# CS-HAT_V2.net
KiCad netlist of a schematic drawn in EAGLE
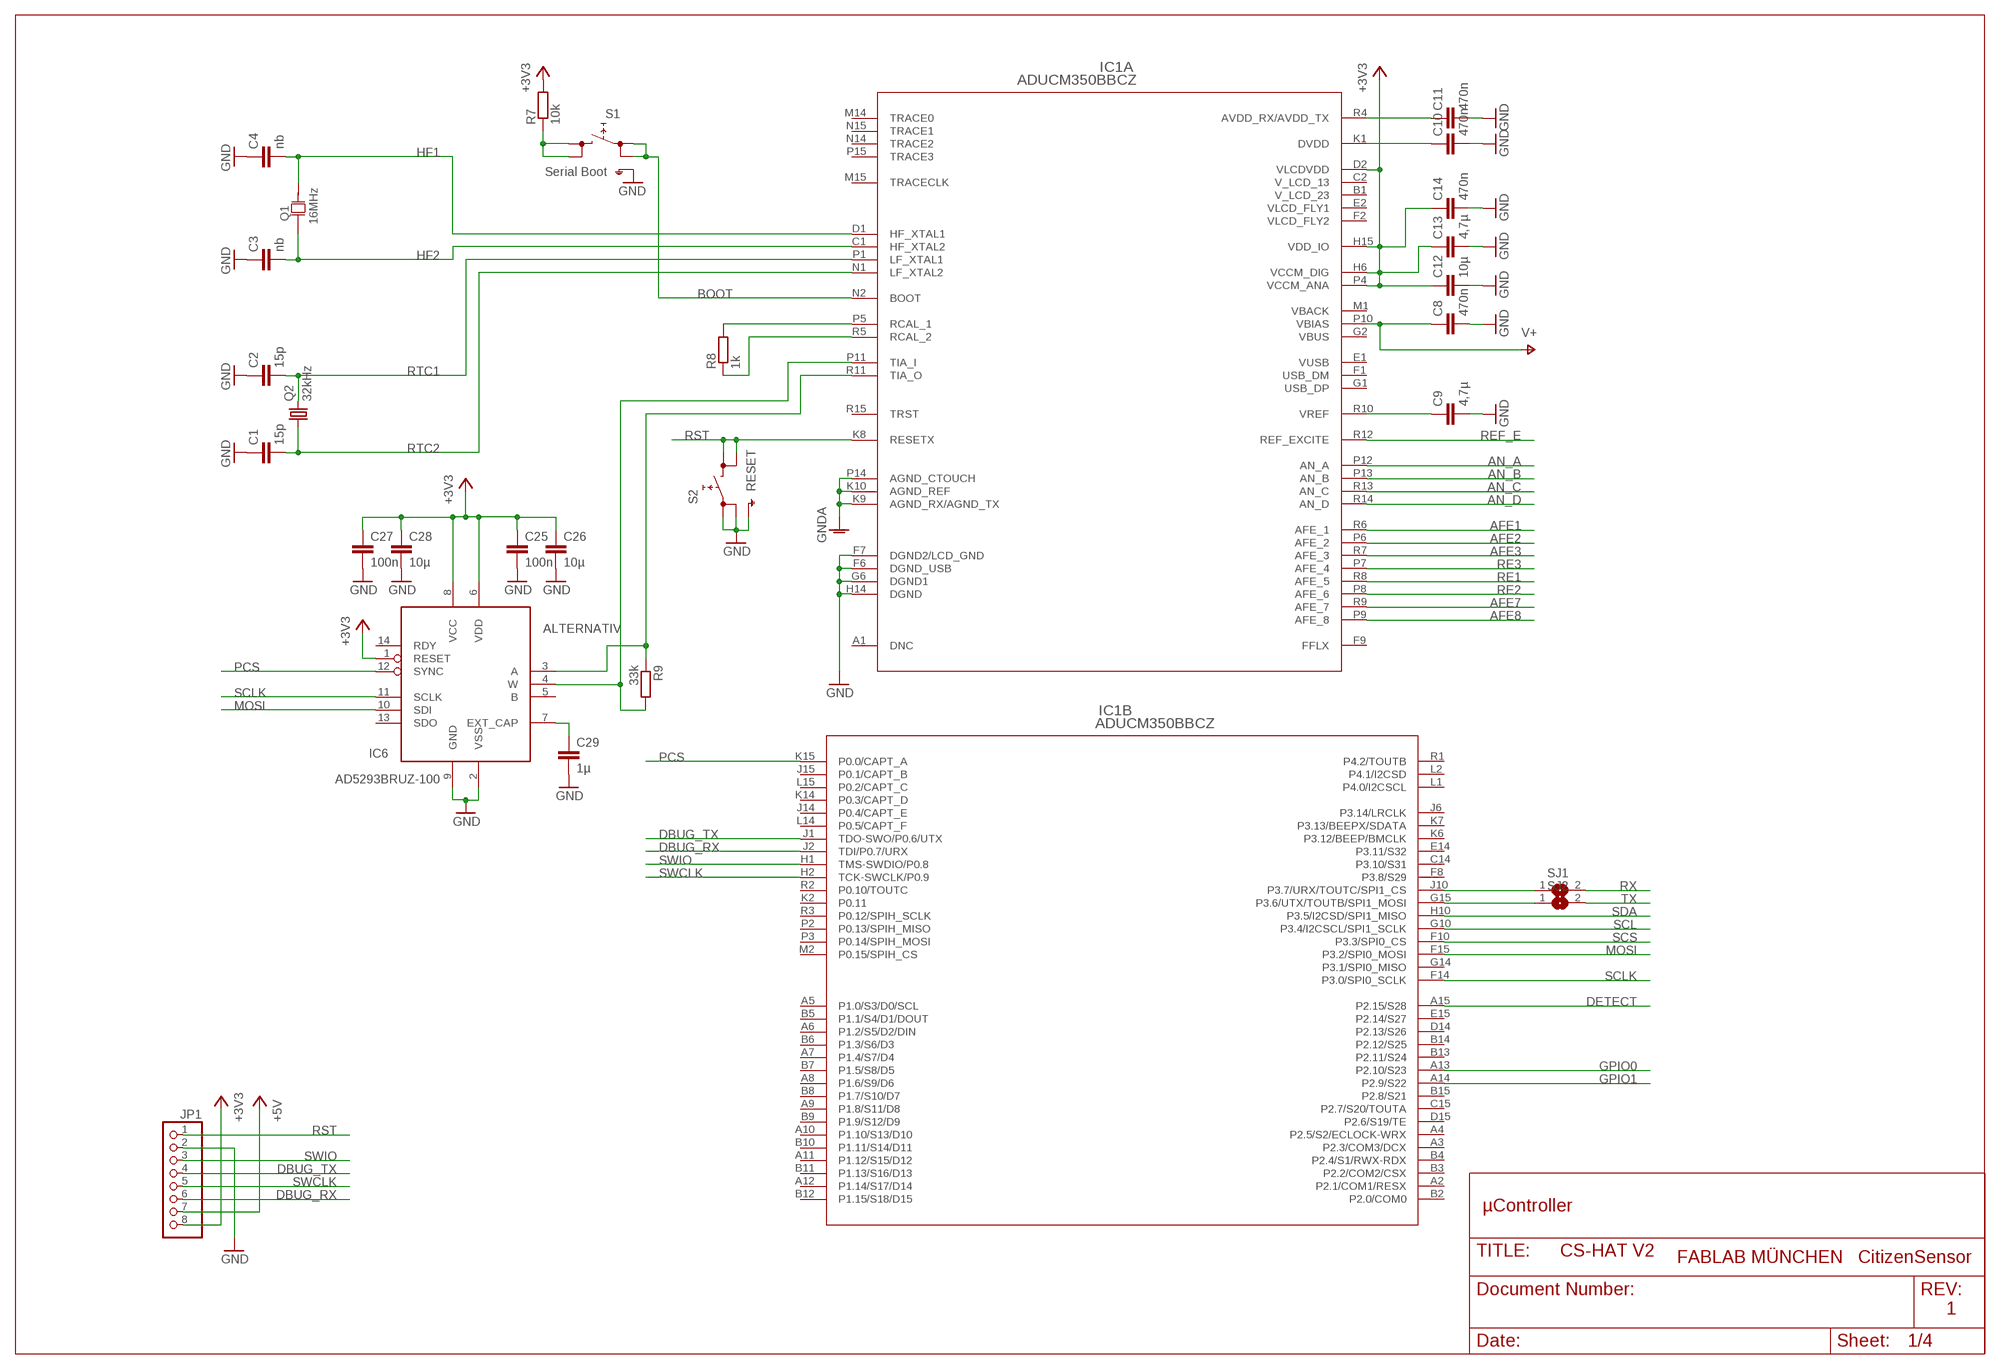
[diagram p0: schematic, sheet 1]
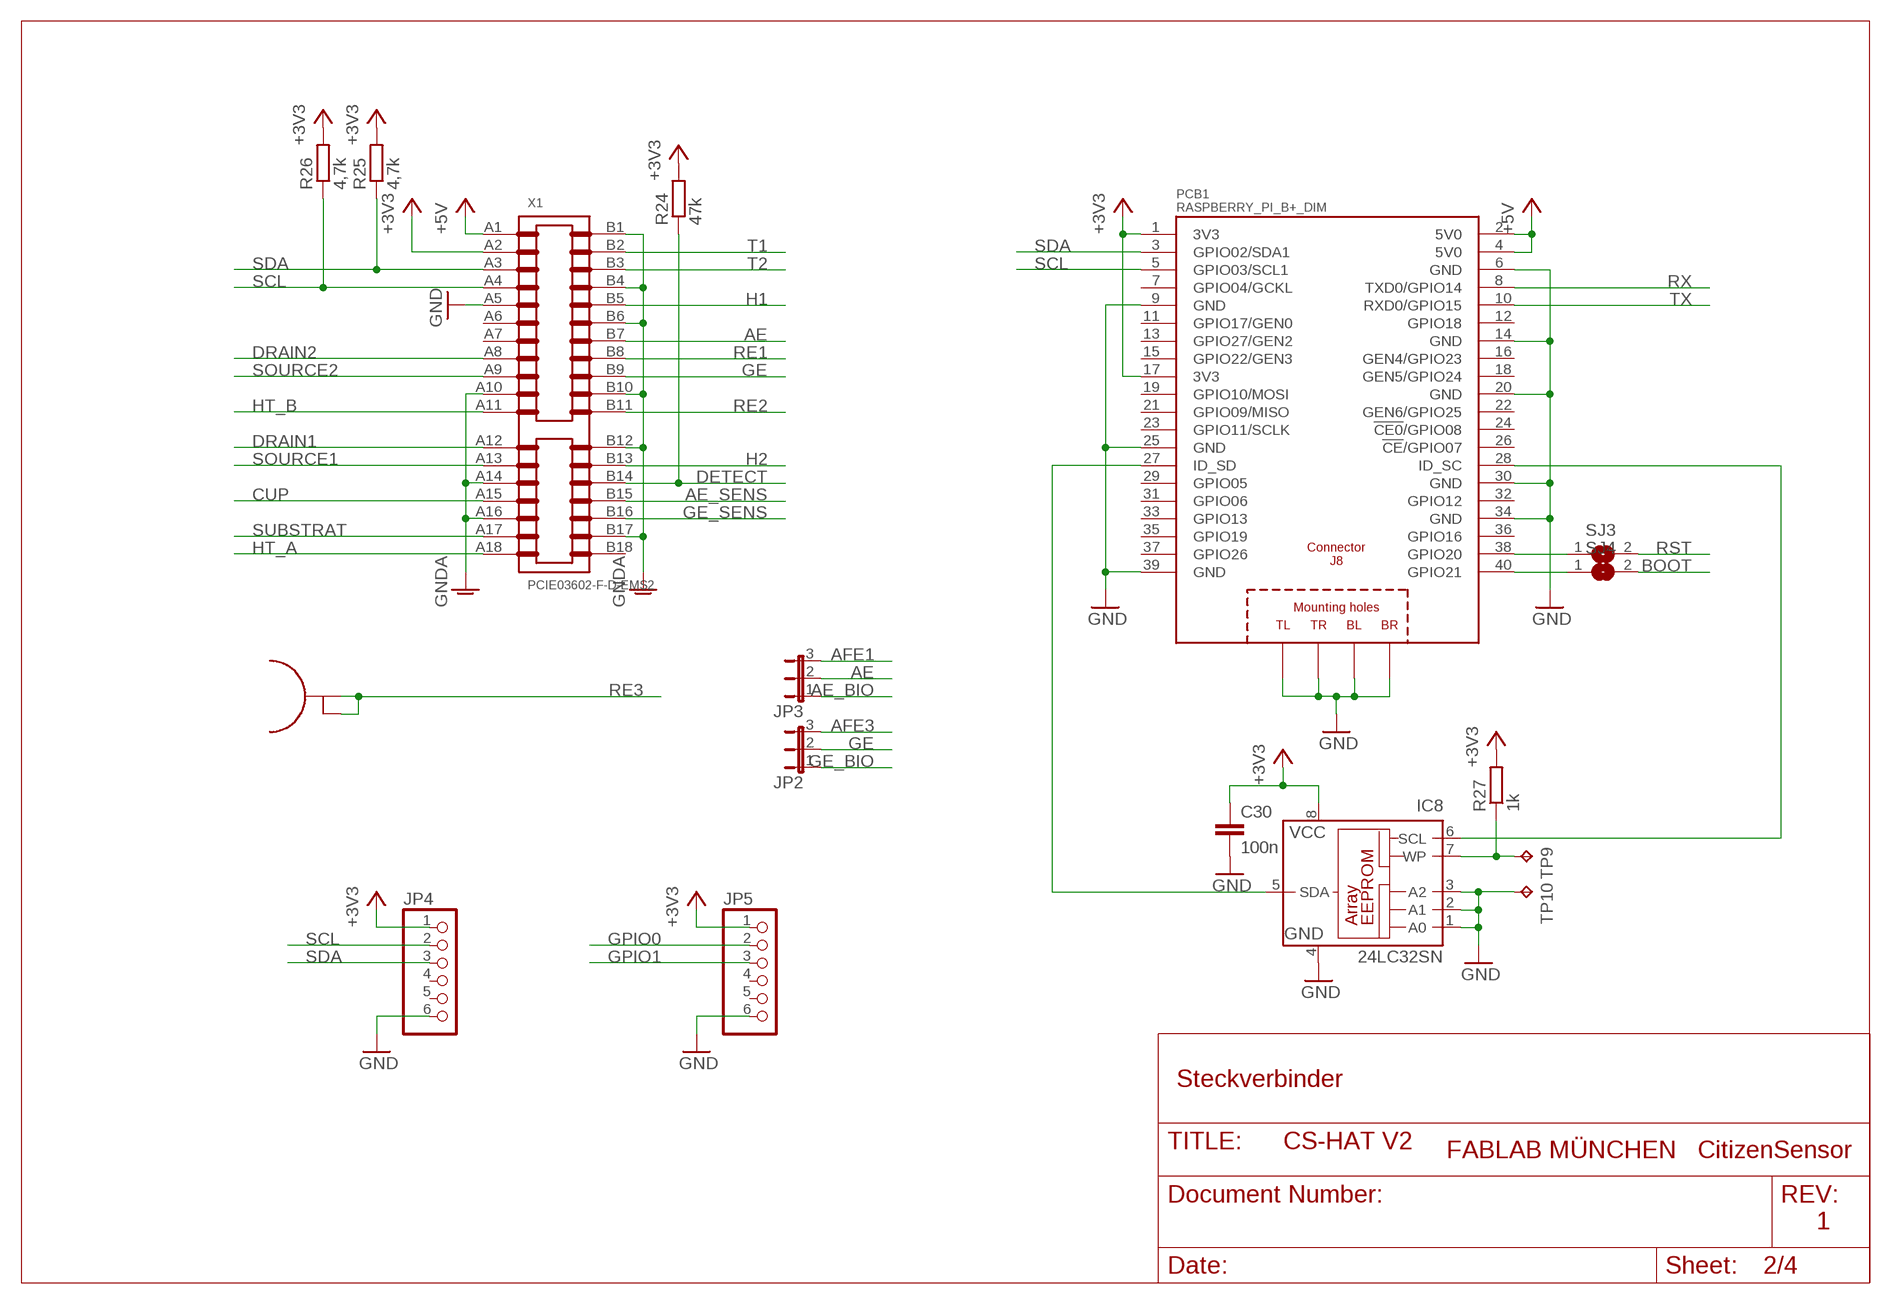
[diagram p1: schematic, sheet 2]
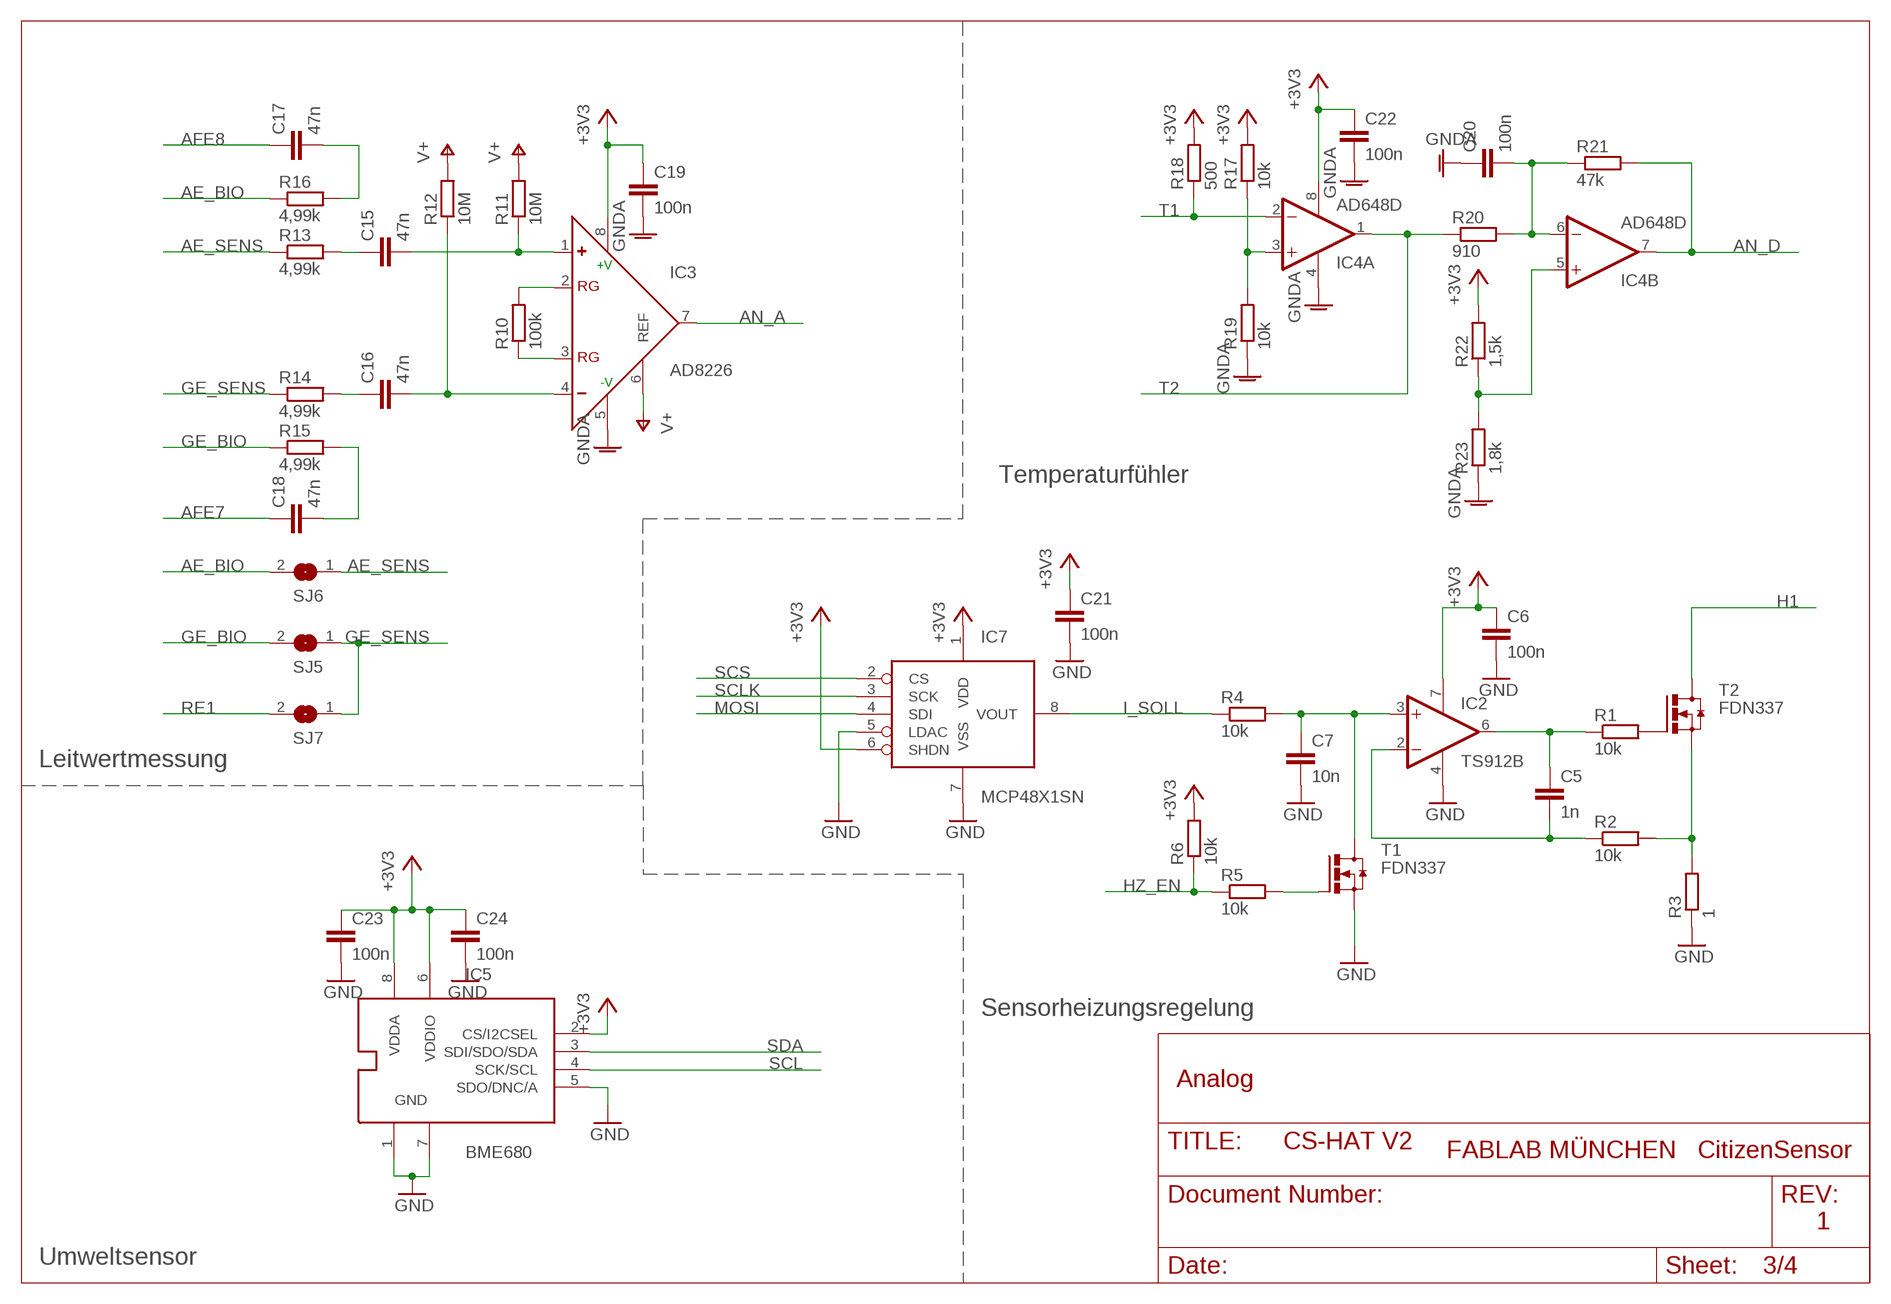
[diagram p2: schematic, sheet 3]
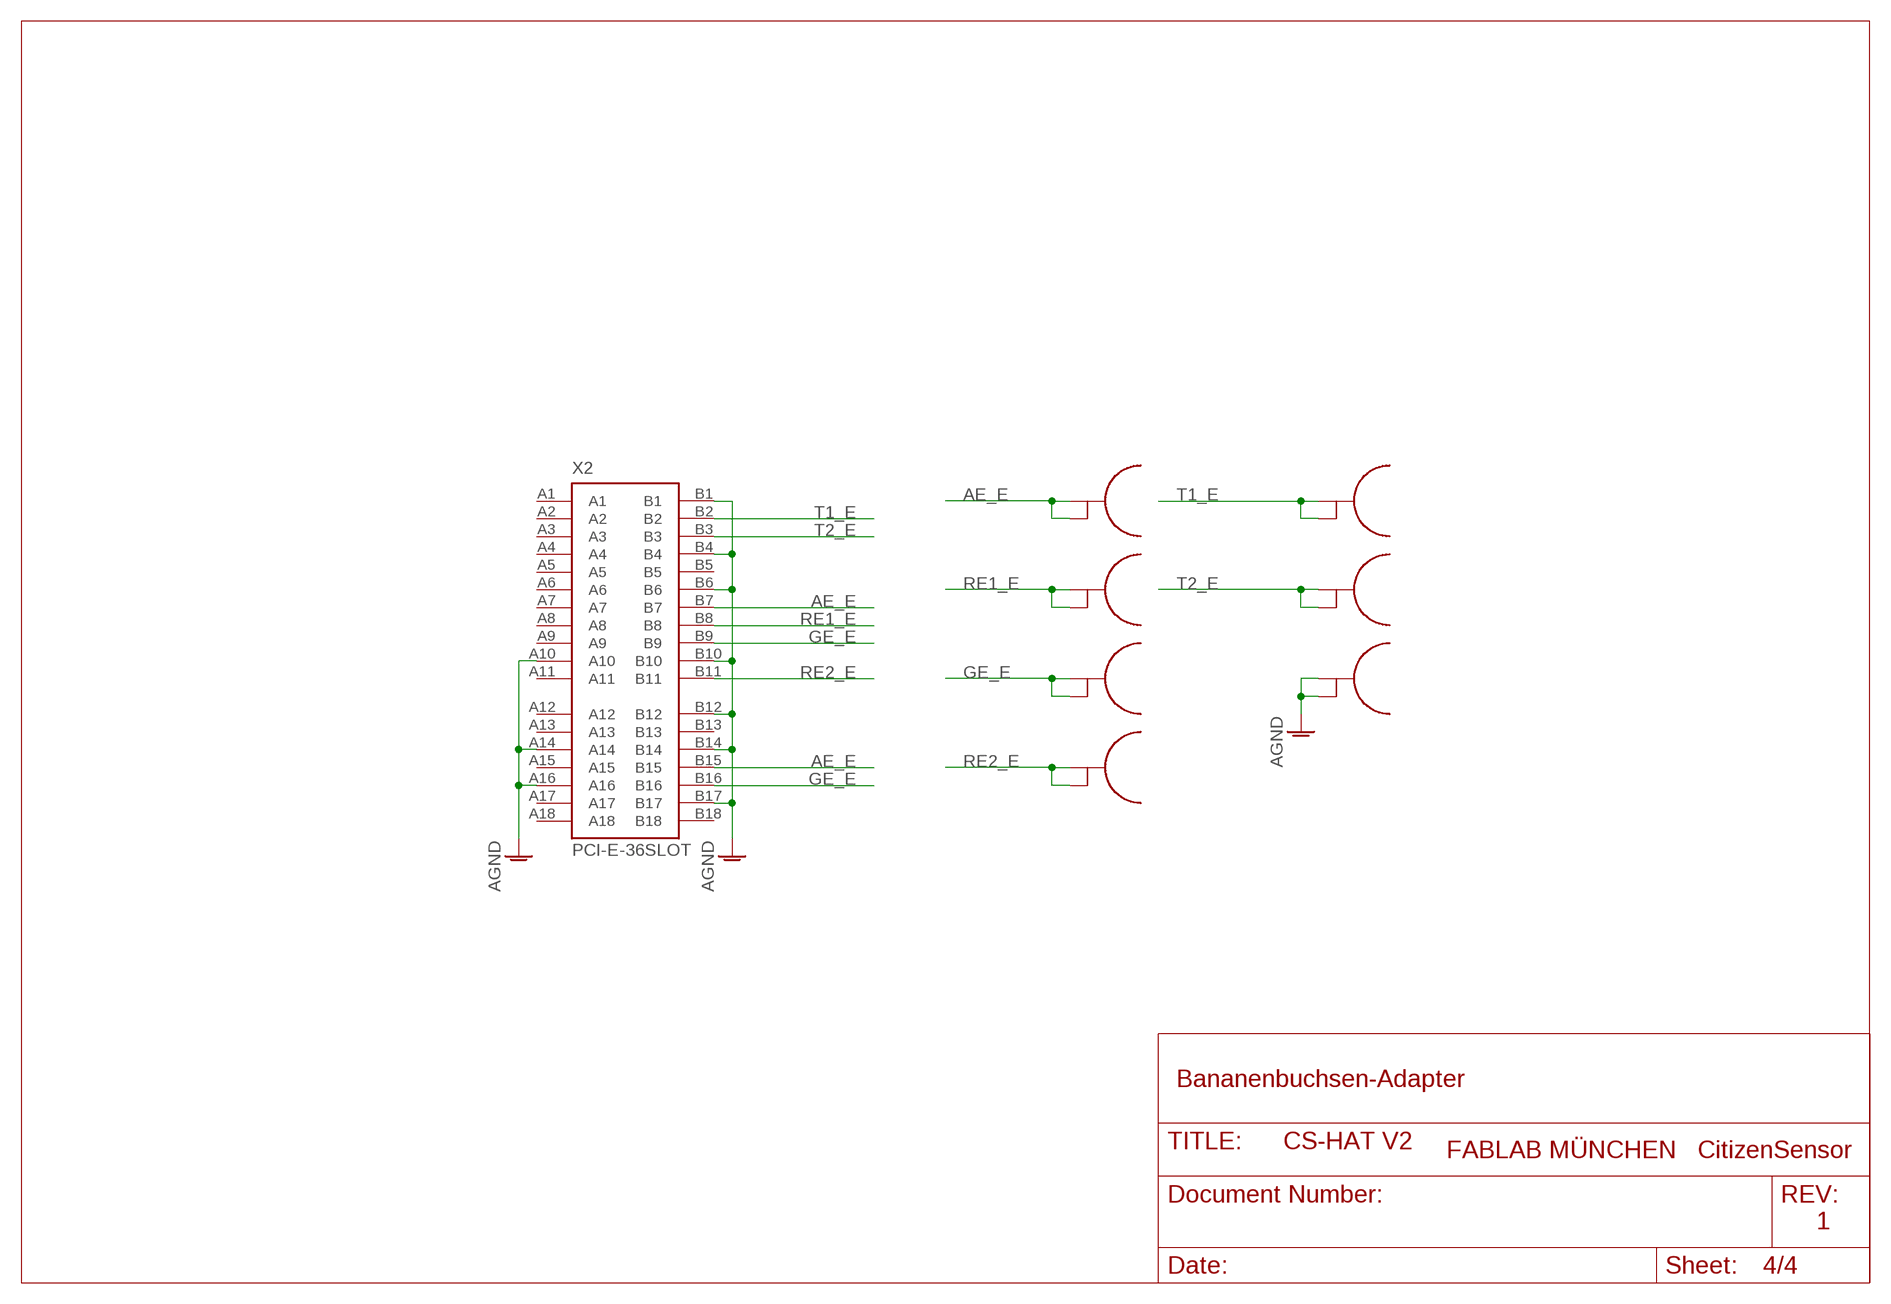
[diagram p3: schematic, sheet 4]

(export (version "E")
  (design (tool "Eeschema 10.0.6"))
  (components
    (comp (ref "C30")
      (value "100n")
      (footprint "eagle-import:C0805")
      (libsource (lib "eagle-import") (part "C-EUC0805"))
    )
    (comp (ref "IC8")
      (value "24LC32SN")
      (footprint "eagle-import:SO-08")
      (fields (field (name "MPN") "M24C04-WMN6P"))
      (libsource (lib "eagle-import") (part "24CSN04"))
    )
    (comp (ref "JP2")
      (value "JP2ES")
      (footprint "eagle-import:JP2S")
      (libsource (lib "eagle-import") (part "JP2ES"))
    )
    (comp (ref "JP3")
      (value "JP2ES")
      (footprint "eagle-import:JP2S")
      (libsource (lib "eagle-import") (part "JP2ES"))
    )
    (comp (ref "JP4")
      (value "PINHD-1X6S")
      (footprint "eagle-import:1X06S")
      (libsource (lib "eagle-import") (part "PINHD-1X6S"))
    )
    (comp (ref "JP5")
      (value "PINHD-1X6S")
      (footprint "eagle-import:1X06S")
      (libsource (lib "eagle-import") (part "PINHD-1X6S"))
    )
    (comp (ref "PCB1")
      (value "RASPBERRY_PI_B+_DIM")
      (footprint "eagle-import:RASPBERRY_PI_BPLUS_DIM")
      (libsource (lib "eagle-import") (part "RASPBERRY_PI_B+_DIM"))
    )
    (comp (ref "R24")
      (value "47k")
      (footprint "eagle-import:R0805")
      (libsource (lib "eagle-import") (part "R-EU_R0805"))
    )
    (comp (ref "R25")
      (value "4,7k")
      (footprint "eagle-import:R0805")
      (libsource (lib "eagle-import") (part "R-EU_R0805"))
    )
    (comp (ref "R26")
      (value "4,7k")
      (footprint "eagle-import:R0805")
      (libsource (lib "eagle-import") (part "R-EU_R0805"))
    )
    (comp (ref "R27")
      (value "1k")
      (footprint "eagle-import:R0805")
      (libsource (lib "eagle-import") (part "R-EU_R0805"))
    )
    (comp (ref "SJ3") (value "SJ") (footprint "eagle-import:SJ") (libsource (lib "eagle-import") (part "SJ")))
    (comp (ref "SJ4") (value "SJ") (footprint "eagle-import:SJ") (libsource (lib "eagle-import") (part "SJ")))
    (comp (ref "TP8")
      (value "TESTPLUG2MM")
      (footprint "eagle-import:TESTPLUG2MM")
      (libsource (lib "eagle-import") (part "TESTPLUG2MM"))
    )
    (comp (ref "TP9")
      (value "TPB2,54")
      (footprint "eagle-import:B2,54")
      (libsource (lib "eagle-import") (part "TPB2,54"))
    )
    (comp (ref "TP10")
      (value "TPB2,54")
      (footprint "eagle-import:B2,54")
      (libsource (lib "eagle-import") (part "TPB2,54"))
    )
    (comp (ref "X1")
      (value "PCIE03602-F-D-EMS2")
      (footprint "eagle-import:PCIE-036-02-F-D-EMS2")
      (libsource (lib "eagle-import") (part "PCIE03602-F-D-EMS2"))
    )
    (comp (ref "C1")
      (value "15p")
      (footprint "eagle-import:C0805")
      (libsource (lib "eagle-import") (part "C-EUC0805"))
    )
    (comp (ref "C2")
      (value "15p")
      (footprint "eagle-import:C0805")
      (libsource (lib "eagle-import") (part "C-EUC0805"))
    )
    (comp (ref "C3")
      (value "nb")
      (footprint "eagle-import:C0805")
      (libsource (lib "eagle-import") (part "C-EUC0805"))
    )
    (comp (ref "C4")
      (value "nb")
      (footprint "eagle-import:C0805")
      (libsource (lib "eagle-import") (part "C-EUC0805"))
    )
    (comp (ref "C8")
      (value "470n")
      (footprint "eagle-import:C0805")
      (libsource (lib "eagle-import") (part "C-EUC0805"))
    )
    (comp (ref "C9")
      (value "4,7µ")
      (footprint "eagle-import:C1206")
      (libsource (lib "eagle-import") (part "C-EUC1206"))
    )
    (comp (ref "C10")
      (value "470n")
      (footprint "eagle-import:C0805")
      (libsource (lib "eagle-import") (part "C-EUC0805"))
    )
    (comp (ref "C11")
      (value "470n")
      (footprint "eagle-import:C0805")
      (libsource (lib "eagle-import") (part "C-EUC0805"))
    )
    (comp (ref "C12")
      (value "10µ")
      (footprint "eagle-import:C1206")
      (libsource (lib "eagle-import") (part "C-EUC1206"))
    )
    (comp (ref "C13")
      (value "4,7µ")
      (footprint "eagle-import:C1206")
      (libsource (lib "eagle-import") (part "C-EUC1206"))
    )
    (comp (ref "C14")
      (value "470n")
      (footprint "eagle-import:C0805")
      (libsource (lib "eagle-import") (part "C-EUC0805"))
    )
    (comp (ref "C25")
      (value "100n")
      (footprint "eagle-import:C0805")
      (libsource (lib "eagle-import") (part "C-EUC0805"))
    )
    (comp (ref "C26")
      (value "10µ")
      (footprint "eagle-import:C1206")
      (libsource (lib "eagle-import") (part "C-EUC1206"))
    )
    (comp (ref "C27")
      (value "100n")
      (footprint "eagle-import:C0805")
      (libsource (lib "eagle-import") (part "C-EUC0805"))
    )
    (comp (ref "C28")
      (value "10µ")
      (footprint "eagle-import:C1206")
      (libsource (lib "eagle-import") (part "C-EUC1206"))
    )
    (comp (ref "C29")
      (value "1µ")
      (footprint "eagle-import:C1206")
      (libsource (lib "eagle-import") (part "C-EUC1206"))
    )
    (comp (ref "IC1")
      (value "ADUCM350BBCZ")
      (footprint "eagle-import:BC_120_3")
      (libsource (lib "eagle-import") (part "ADUCM350BBCZ"))
    )
    (comp (ref "IC6")
      (value "AD5293BRUZ-100")
      (footprint "eagle-import:TSSOP14")
      (libsource (lib "eagle-import") (part "AD5293BRUZ"))
    )
    (comp (ref "JP1")
      (value "PINHD-1X8S")
      (footprint "eagle-import:1X08S")
      (libsource (lib "eagle-import") (part "PINHD-1X8S"))
    )
    (comp (ref "Q1")
      (value "16MHz")
      (footprint "eagle-import:JXS53")
      (libsource (lib "eagle-import") (part "JXS53"))
    )
    (comp (ref "Q2")
      (value "32kHz")
      (footprint "eagle-import:FC-12M")
      (libsource (lib "eagle-import") (part "FC-12M"))
    )
    (comp (ref "R7")
      (value "10k")
      (footprint "eagle-import:R0805")
      (libsource (lib "eagle-import") (part "R-EU_R0805"))
    )
    (comp (ref "R8")
      (value "1k")
      (footprint "eagle-import:R0805")
      (libsource (lib "eagle-import") (part "R-EU_R0805"))
    )
    (comp (ref "R9")
      (value "33k")
      (footprint "eagle-import:R0805")
      (libsource (lib "eagle-import") (part "R-EU_R0805"))
    )
    (comp (ref "S1")
      (value "Serial Boot")
      (footprint "eagle-import:SKHMPXE010")
      (libsource (lib "eagle-import") (part "SKHMPE010S"))
    )
    (comp (ref "S2")
      (value "RESET")
      (footprint "eagle-import:SKHMPXE010")
      (libsource (lib "eagle-import") (part "SKHMPE010S"))
    )
    (comp (ref "SJ1") (value "SJ") (footprint "eagle-import:SJ") (libsource (lib "eagle-import") (part "SJ")))
    (comp (ref "SJ2") (value "SJ") (footprint "eagle-import:SJ") (libsource (lib "eagle-import") (part "SJ")))
    (comp (ref "TP1")
      (value "TESTPLUG2MM")
      (footprint "eagle-import:TESTPLUG2MM")
      (libsource (lib "eagle-import") (part "TESTPLUG2MM"))
    )
    (comp (ref "TP2")
      (value "TESTPLUG2MM")
      (footprint "eagle-import:TESTPLUG2MM")
      (libsource (lib "eagle-import") (part "TESTPLUG2MM"))
    )
    (comp (ref "TP3")
      (value "TESTPLUG2MM")
      (footprint "eagle-import:TESTPLUG2MM")
      (libsource (lib "eagle-import") (part "TESTPLUG2MM"))
    )
    (comp (ref "TP4")
      (value "TESTPLUG2MM")
      (footprint "eagle-import:TESTPLUG2MM")
      (libsource (lib "eagle-import") (part "TESTPLUG2MM"))
    )
    (comp (ref "TP5")
      (value "TESTPLUG2MM")
      (footprint "eagle-import:TESTPLUG2MM")
      (libsource (lib "eagle-import") (part "TESTPLUG2MM"))
    )
    (comp (ref "TP6")
      (value "TESTPLUG2MM")
      (footprint "eagle-import:TESTPLUG2MM")
      (libsource (lib "eagle-import") (part "TESTPLUG2MM"))
    )
    (comp (ref "TP7")
      (value "TESTPLUG2MM")
      (footprint "eagle-import:TESTPLUG2MM")
      (libsource (lib "eagle-import") (part "TESTPLUG2MM"))
    )
    (comp (ref "X2")
      (value "PCI-E-36SLOT")
      (footprint "eagle-import:PCI-E-36_SLOT")
      (libsource (lib "eagle-import") (part "PCI-E-36SLOT"))
    )
    (comp (ref "C5")
      (value "1n")
      (footprint "eagle-import:C0805")
      (libsource (lib "eagle-import") (part "C-EUC0805"))
    )
    (comp (ref "C6")
      (value "100n")
      (footprint "eagle-import:C0805")
      (libsource (lib "eagle-import") (part "C-EUC0805"))
    )
    (comp (ref "C7")
      (value "10n")
      (footprint "eagle-import:C0805")
      (libsource (lib "eagle-import") (part "C-EUC0805"))
    )
    (comp (ref "C15")
      (value "47n")
      (footprint "eagle-import:C0805")
      (libsource (lib "eagle-import") (part "C-EUC0805"))
    )
    (comp (ref "C16")
      (value "47n")
      (footprint "eagle-import:C0805")
      (libsource (lib "eagle-import") (part "C-EUC0805"))
    )
    (comp (ref "C17")
      (value "47n")
      (footprint "eagle-import:C0805")
      (libsource (lib "eagle-import") (part "C-EUC0805"))
    )
    (comp (ref "C18")
      (value "47n")
      (footprint "eagle-import:C0805")
      (libsource (lib "eagle-import") (part "C-EUC0805"))
    )
    (comp (ref "C19")
      (value "100n")
      (footprint "eagle-import:C0805")
      (libsource (lib "eagle-import") (part "C-EUC0805"))
    )
    (comp (ref "C20")
      (value "100n")
      (footprint "eagle-import:C0805")
      (libsource (lib "eagle-import") (part "C-EUC0805"))
    )
    (comp (ref "C21")
      (value "100n")
      (footprint "eagle-import:C0805")
      (libsource (lib "eagle-import") (part "C-EUC0805"))
    )
    (comp (ref "C22")
      (value "100n")
      (footprint "eagle-import:C0805")
      (libsource (lib "eagle-import") (part "C-EUC0805"))
    )
    (comp (ref "C23")
      (value "100n")
      (footprint "eagle-import:C0805")
      (libsource (lib "eagle-import") (part "C-EUC0805"))
    )
    (comp (ref "C24")
      (value "100n")
      (footprint "eagle-import:C0805")
      (libsource (lib "eagle-import") (part "C-EUC0805"))
    )
    (comp (ref "IC2")
      (value "TS912B")
      (footprint "eagle-import:SO08")
      (libsource (lib "eagle-import") (part "1AMP_P7+4D"))
    )
    (comp (ref "IC3")
      (value "AD8226")
      (footprint "eagle-import:SO8")
      (libsource (lib "eagle-import") (part "AD8226"))
    )
    (comp (ref "IC4")
      (value "AD648D")
      (footprint "eagle-import:SO08")
      (libsource (lib "eagle-import") (part "AD648D"))
    )
    (comp (ref "IC5")
      (value "BME680")
      (footprint "eagle-import:BME680")
      (libsource (lib "eagle-import") (part "BME680"))
    )
    (comp (ref "IC7")
      (value "MCP48X1SN")
      (footprint "eagle-import:SO-08")
      (libsource (lib "eagle-import") (part "MCP48X1SN"))
    )
    (comp (ref "R1")
      (value "10k")
      (footprint "eagle-import:R0805")
      (libsource (lib "eagle-import") (part "R-EU_R0805"))
    )
    (comp (ref "R2")
      (value "10k")
      (footprint "eagle-import:R0805")
      (libsource (lib "eagle-import") (part "R-EU_R0805"))
    )
    (comp (ref "R3")
      (value "1")
      (footprint "eagle-import:R1210")
      (libsource (lib "eagle-import") (part "R-EU_R1210"))
    )
    (comp (ref "R4")
      (value "10k")
      (footprint "eagle-import:R0805")
      (libsource (lib "eagle-import") (part "R-EU_R0805"))
    )
    (comp (ref "R5")
      (value "10k")
      (footprint "eagle-import:R0805")
      (libsource (lib "eagle-import") (part "R-EU_R0805"))
    )
    (comp (ref "R6")
      (value "10k")
      (footprint "eagle-import:R0805")
      (libsource (lib "eagle-import") (part "R-EU_R0805"))
    )
    (comp (ref "R10")
      (value "100k")
      (footprint "eagle-import:R0805")
      (libsource (lib "eagle-import") (part "R-EU_R0805"))
    )
    (comp (ref "R11")
      (value "10M")
      (footprint "eagle-import:R0805")
      (libsource (lib "eagle-import") (part "R-EU_R0805"))
    )
    (comp (ref "R12")
      (value "10M")
      (footprint "eagle-import:R0805")
      (libsource (lib "eagle-import") (part "R-EU_R0805"))
    )
    (comp (ref "R13")
      (value "4,99k")
      (footprint "eagle-import:R0805")
      (libsource (lib "eagle-import") (part "R-EU_R0805"))
    )
    (comp (ref "R14")
      (value "4,99k")
      (footprint "eagle-import:R0805")
      (libsource (lib "eagle-import") (part "R-EU_R0805"))
    )
    (comp (ref "R15")
      (value "4,99k")
      (footprint "eagle-import:R0805")
      (libsource (lib "eagle-import") (part "R-EU_R0805"))
    )
    (comp (ref "R16")
      (value "4,99k")
      (footprint "eagle-import:R0805")
      (libsource (lib "eagle-import") (part "R-EU_R0805"))
    )
    (comp (ref "R17")
      (value "10k")
      (footprint "eagle-import:R0805")
      (libsource (lib "eagle-import") (part "R-EU_R0805"))
    )
    (comp (ref "R18")
      (value "500")
      (footprint "eagle-import:R0805")
      (libsource (lib "eagle-import") (part "R-EU_R0805"))
    )
    (comp (ref "R19")
      (value "10k")
      (footprint "eagle-import:R0805")
      (libsource (lib "eagle-import") (part "R-EU_R0805"))
    )
    (comp (ref "R20")
      (value "910")
      (footprint "eagle-import:R0805")
      (libsource (lib "eagle-import") (part "R-EU_R0805"))
    )
    (comp (ref "R21")
      (value "47k")
      (footprint "eagle-import:R0805")
      (libsource (lib "eagle-import") (part "R-EU_R0805"))
    )
    (comp (ref "R22")
      (value "1,5k")
      (footprint "eagle-import:R0805")
      (libsource (lib "eagle-import") (part "R-EU_R0805"))
    )
    (comp (ref "R23")
      (value "1,8k")
      (footprint "eagle-import:R0805")
      (libsource (lib "eagle-import") (part "R-EU_R0805"))
    )
    (comp (ref "SJ5") (value "SJ") (footprint "eagle-import:SJ") (libsource (lib "eagle-import") (part "SJ")))
    (comp (ref "SJ6") (value "SJ") (footprint "eagle-import:SJ") (libsource (lib "eagle-import") (part "SJ")))
    (comp (ref "SJ7") (value "SJ") (footprint "eagle-import:SJ") (libsource (lib "eagle-import") (part "SJ")))
    (comp (ref "T1")
      (value "FDN337")
      (footprint "eagle-import:SUPER-SOT3")
      (libsource (lib "eagle-import") (part "FDN337"))
    )
    (comp (ref "T2")
      (value "FDN337")
      (footprint "eagle-import:SUPER-SOT3")
      (libsource (lib "eagle-import") (part "FDN337"))
    )
  )
  (nets
    (net (code "1") (name "+3V3") (class "Default")
      (node (ref "C12") (pin "1") (pinfunction "1_1") (pintype "passive"))
      (node (ref "C13") (pin "1") (pinfunction "1_1") (pintype "passive"))
      (node (ref "C14") (pin "1") (pinfunction "1_1") (pintype "passive"))
      (node (ref "C19") (pin "1") (pinfunction "1_1") (pintype "passive"))
      (node (ref "C21") (pin "1") (pinfunction "1_1") (pintype "passive"))
      (node (ref "C22") (pin "1") (pinfunction "1_1") (pintype "passive"))
      (node (ref "C23") (pin "1") (pinfunction "1_1") (pintype "passive"))
      (node (ref "C24") (pin "1") (pinfunction "1_1") (pintype "passive"))
      (node (ref "C25") (pin "1") (pinfunction "1_1") (pintype "passive"))
      (node (ref "C26") (pin "1") (pinfunction "1_1") (pintype "passive"))
      (node (ref "C27") (pin "1") (pinfunction "1_1") (pintype "passive"))
      (node (ref "C28") (pin "1") (pinfunction "1_1") (pintype "passive"))
      (node (ref "C30") (pin "1") (pinfunction "1_1") (pintype "passive"))
      (node (ref "C6") (pin "1") (pinfunction "1_1") (pintype "passive"))
      (node (ref "IC1") (pin "D2") (pinfunction "VLCDVDD_D2") (pintype "passive"))
      (node (ref "IC1") (pin "H15") (pinfunction "VDD_IO_H15") (pintype "passive"))
      (node (ref "IC1") (pin "H6") (pinfunction "VCCM_DIG_H6") (pintype "passive"))
      (node (ref "IC1") (pin "P4") (pinfunction "VCCM_ANA_P4") (pintype "passive"))
      (node (ref "IC2") (pin "7") (pinfunction "V+_7") (pintype "power_in"))
      (node (ref "IC3") (pin "8") (pinfunction "+V_8") (pintype "power_in"))
      (node (ref "IC4") (pin "8") (pinfunction "V+_8") (pintype "power_in"))
      (node (ref "IC5") (pin "2") (pinfunction "CS/I2CSEL_2") (pintype "input"))
      (node (ref "IC5") (pin "6") (pinfunction "VDDIO_6") (pintype "power_in"))
      (node (ref "IC5") (pin "8") (pinfunction "VDDA_8") (pintype "power_in"))
      (node (ref "IC6") (pin "1") (pinfunction "RESET_1") (pintype "input"))
      (node (ref "IC6") (pin "6") (pinfunction "VDD_6") (pintype "power_in"))
      (node (ref "IC6") (pin "8") (pinfunction "VCC_8") (pintype "power_in"))
      (node (ref "IC7") (pin "1") (pinfunction "VDD_1") (pintype "power_in"))
      (node (ref "IC7") (pin "6") (pinfunction "SHDN_6") (pintype "input"))
      (node (ref "IC8") (pin "8") (pinfunction "VCC_8") (pintype "power_in"))
      (node (ref "JP1") (pin "8") (pinfunction "8_8") (pintype "passive"))
      (node (ref "JP4") (pin "1") (pinfunction "1_1") (pintype "passive"))
      (node (ref "JP5") (pin "1") (pinfunction "1_1") (pintype "passive"))
      (node (ref "PCB1") (pin "1") (pinfunction "3V3_1") (pintype "power_in"))
      (node (ref "PCB1") (pin "17") (pinfunction "3V3_17") (pintype "power_in"))
      (node (ref "R17") (pin "2") (pinfunction "2_2") (pintype "passive"))
      (node (ref "R18") (pin "2") (pinfunction "2_2") (pintype "passive"))
      (node (ref "R22") (pin "2") (pinfunction "2_2") (pintype "passive"))
      (node (ref "R24") (pin "2") (pinfunction "2_2") (pintype "passive"))
      (node (ref "R25") (pin "2") (pinfunction "2_2") (pintype "passive"))
      (node (ref "R26") (pin "2") (pinfunction "2_2") (pintype "passive"))
      (node (ref "R27") (pin "2") (pinfunction "2_2") (pintype "passive"))
      (node (ref "R6") (pin "2") (pinfunction "2_2") (pintype "passive"))
      (node (ref "R7") (pin "2") (pinfunction "2_2") (pintype "passive"))
      (node (ref "X1") (pin "A2") (pinfunction "A2_A2") (pintype "passive"))
    )
    (net (code "2") (name "+5V") (class "Default")
      (node (ref "JP1") (pin "7") (pinfunction "7_7") (pintype "passive"))
      (node (ref "PCB1") (pin "2") (pinfunction "5V0_2") (pintype "power_in"))
      (node (ref "PCB1") (pin "4") (pinfunction "5V0_4") (pintype "power_in"))
      (node (ref "X1") (pin "A1") (pinfunction "A1_A1") (pintype "passive"))
    )
    (net (code "3") (name "AE") (class "Default")
      (node (ref "JP3") (pin "2") (pinfunction "2_2") (pintype "passive"))
      (node (ref "X1") (pin "B7") (pinfunction "B7_B7") (pintype "passive"))
    )
    (net (code "4") (name "AE_BIO") (class "Default")
      (node (ref "JP3") (pin "1") (pinfunction "1_1") (pintype "passive"))
      (node (ref "R16") (pin "1") (pinfunction "1_1") (pintype "passive"))
      (node (ref "SJ6") (pin "2") (pinfunction "2_2") (pintype "passive"))
    )
    (net (code "5") (name "AE_E") (class "Default")
      (node (ref "TP1") (pin "A") (pinfunction "P$1_A") (pintype "passive"))
      (node (ref "TP1") (pin "B") (pinfunction "P$2_B") (pintype "passive"))
      (node (ref "X2") (pin "B15") (pinfunction "B15_B15") (pintype "passive"))
      (node (ref "X2") (pin "B7") (pinfunction "B7_B7") (pintype "passive"))
    )
    (net (code "6") (name "AE_SENS") (class "Default")
      (node (ref "R13") (pin "1") (pinfunction "1_1") (pintype "passive"))
      (node (ref "SJ6") (pin "1") (pinfunction "1_1") (pintype "passive"))
      (node (ref "X1") (pin "B15") (pinfunction "B15_B15") (pintype "passive"))
    )
    (net (code "7") (name "AFE1") (class "Default")
      (node (ref "IC1") (pin "R6") (pinfunction "AFE_1_R6") (pintype "passive"))
      (node (ref "JP3") (pin "3") (pinfunction "3_3") (pintype "passive"))
    )
    (net (code "8") (name "AFE2") (class "Default")
      (node (ref "IC1") (pin "P6") (pinfunction "AFE_2_P6") (pintype "passive"))
    )
    (net (code "9") (name "AFE3") (class "Default")
      (node (ref "IC1") (pin "R7") (pinfunction "AFE_3_R7") (pintype "passive"))
      (node (ref "JP2") (pin "3") (pinfunction "3_3") (pintype "passive"))
    )
    (net (code "10") (name "AFE7") (class "Default")
      (node (ref "C18") (pin "1") (pinfunction "1_1") (pintype "passive"))
      (node (ref "IC1") (pin "R9") (pinfunction "AFE_7_R9") (pintype "passive"))
    )
    (net (code "11") (name "AFE8") (class "Default")
      (node (ref "C17") (pin "1") (pinfunction "1_1") (pintype "passive"))
      (node (ref "IC1") (pin "P9") (pinfunction "AFE_8_P9") (pintype "passive"))
    )
    (net (code "12") (name "AGND") (class "Default")
      (node (ref "TP7") (pin "A") (pinfunction "P$1_A") (pintype "passive"))
      (node (ref "TP7") (pin "B") (pinfunction "P$2_B") (pintype "passive"))
      (node (ref "X2") (pin "A10") (pinfunction "A10_A10") (pintype "passive"))
      (node (ref "X2") (pin "A14") (pinfunction "A14_A14") (pintype "passive"))
      (node (ref "X2") (pin "A16") (pinfunction "A16_A16") (pintype "passive"))
      (node (ref "X2") (pin "B1") (pinfunction "B1_B1") (pintype "passive"))
      (node (ref "X2") (pin "B10") (pinfunction "B10_B10") (pintype "passive"))
      (node (ref "X2") (pin "B12") (pinfunction "B12_B12") (pintype "passive"))
      (node (ref "X2") (pin "B14") (pinfunction "B14_B14") (pintype "passive"))
      (node (ref "X2") (pin "B17") (pinfunction "B17_B17") (pintype "passive"))
      (node (ref "X2") (pin "B4") (pinfunction "B4_B4") (pintype "passive"))
      (node (ref "X2") (pin "B6") (pinfunction "B6_B6") (pintype "passive"))
    )
    (net (code "13") (name "AN_A") (class "Default")
      (node (ref "IC1") (pin "P12") (pinfunction "AN_A_P12") (pintype "passive"))
      (node (ref "IC3") (pin "7") (pinfunction "OUT_7") (pintype "output"))
    )
    (net (code "14") (name "AN_B") (class "Default")
      (node (ref "IC1") (pin "P13") (pinfunction "AN_B_P13") (pintype "passive"))
    )
    (net (code "15") (name "AN_C") (class "Default")
      (node (ref "IC1") (pin "R13") (pinfunction "AN_C_R13") (pintype "passive"))
    )
    (net (code "16") (name "AN_D") (class "Default")
      (node (ref "IC1") (pin "R14") (pinfunction "AN_D_R14") (pintype "passive"))
      (node (ref "IC4") (pin "7") (pinfunction "OUT_7") (pintype "output"))
      (node (ref "R21") (pin "2") (pinfunction "2_2") (pintype "passive"))
    )
    (net (code "17") (name "BOOT") (class "Default")
      (node (ref "IC1") (pin "N2") (pinfunction "BOOT_N2") (pintype "passive"))
      (node (ref "S1") (pin "1") (pinfunction "1.1_1") (pintype "passive"))
      (node (ref "S1") (pin "2") (pinfunction "1.2_2") (pintype "passive"))
      (node (ref "SJ4") (pin "2") (pinfunction "2_2") (pintype "passive"))
    )
    (net (code "18") (name "CUP") (class "Default")
      (node (ref "X1") (pin "A15") (pinfunction "A15_A15") (pintype "passive"))
    )
    (net (code "19") (name "DBUG_RX") (class "Default")
      (node (ref "IC1") (pin "J2") (pinfunction "TDI/P0.7/URX_J2") (pintype "passive"))
      (node (ref "JP1") (pin "6") (pinfunction "6_6") (pintype "passive"))
    )
    (net (code "20") (name "DBUG_TX") (class "Default")
      (node (ref "IC1") (pin "J1") (pinfunction "TDO-SWO/P0.6/UTX_J1") (pintype "passive"))
      (node (ref "JP1") (pin "4") (pinfunction "4_4") (pintype "passive"))
    )
    (net (code "21") (name "DETECT") (class "Default")
      (node (ref "IC1") (pin "A15") (pinfunction "P2.15/S28_A15") (pintype "passive"))
      (node (ref "R24") (pin "1") (pinfunction "1_1") (pintype "passive"))
      (node (ref "X1") (pin "B14") (pinfunction "B14_B14") (pintype "passive"))
    )
    (net (code "22") (name "DRAIN1") (class "Default")
      (node (ref "X1") (pin "A12") (pinfunction "A12_A12") (pintype "passive"))
    )
    (net (code "23") (name "DRAIN2") (class "Default")
      (node (ref "X1") (pin "A8") (pinfunction "A8_A8") (pintype "passive"))
    )
    (net (code "24") (name "GE") (class "Default")
      (node (ref "JP2") (pin "2") (pinfunction "2_2") (pintype "passive"))
      (node (ref "X1") (pin "B9") (pinfunction "B9_B9") (pintype "passive"))
    )
    (net (code "25") (name "GE_BIO") (class "Default")
      (node (ref "JP2") (pin "1") (pinfunction "1_1") (pintype "passive"))
      (node (ref "R15") (pin "1") (pinfunction "1_1") (pintype "passive"))
      (node (ref "SJ5") (pin "2") (pinfunction "2_2") (pintype "passive"))
    )
    (net (code "26") (name "GE_E") (class "Default")
      (node (ref "TP3") (pin "A") (pinfunction "P$1_A") (pintype "passive"))
      (node (ref "TP3") (pin "B") (pinfunction "P$2_B") (pintype "passive"))
      (node (ref "X2") (pin "B16") (pinfunction "B16_B16") (pintype "passive"))
      (node (ref "X2") (pin "B9") (pinfunction "B9_B9") (pintype "passive"))
    )
    (net (code "27") (name "GE_SENS") (class "Default")
      (node (ref "R14") (pin "1") (pinfunction "1_1") (pintype "passive"))
      (node (ref "SJ5") (pin "1") (pinfunction "1_1") (pintype "passive"))
      (node (ref "SJ7") (pin "1") (pinfunction "1_1") (pintype "passive"))
      (node (ref "X1") (pin "B16") (pinfunction "B16_B16") (pintype "passive"))
    )
    (net (code "28") (name "GND") (class "Default")
      (node (ref "C1") (pin "1") (pinfunction "1_1") (pintype "passive"))
      (node (ref "C10") (pin "2") (pinfunction "2_2") (pintype "passive"))
      (node (ref "C11") (pin "2") (pinfunction "2_2") (pintype "passive"))
      (node (ref "C12") (pin "2") (pinfunction "2_2") (pintype "passive"))
      (node (ref "C13") (pin "2") (pinfunction "2_2") (pintype "passive"))
      (node (ref "C14") (pin "2") (pinfunction "2_2") (pintype "passive"))
      (node (ref "C2") (pin "1") (pinfunction "1_1") (pintype "passive"))
      (node (ref "C21") (pin "2") (pinfunction "2_2") (pintype "passive"))
      (node (ref "C23") (pin "2") (pinfunction "2_2") (pintype "passive"))
      (node (ref "C24") (pin "2") (pinfunction "2_2") (pintype "passive"))
      (node (ref "C25") (pin "2") (pinfunction "2_2") (pintype "passive"))
      (node (ref "C26") (pin "2") (pinfunction "2_2") (pintype "passive"))
      (node (ref "C27") (pin "2") (pinfunction "2_2") (pintype "passive"))
      (node (ref "C28") (pin "2") (pinfunction "2_2") (pintype "passive"))
      (node (ref "C29") (pin "2") (pinfunction "2_2") (pintype "passive"))
      (node (ref "C3") (pin "1") (pinfunction "1_1") (pintype "passive"))
      (node (ref "C30") (pin "2") (pinfunction "2_2") (pintype "passive"))
      (node (ref "C4") (pin "1") (pinfunction "1_1") (pintype "passive"))
      (node (ref "C6") (pin "2") (pinfunction "2_2") (pintype "passive"))
      (node (ref "C7") (pin "2") (pinfunction "2_2") (pintype "passive"))
      (node (ref "C8") (pin "2") (pinfunction "2_2") (pintype "passive"))
      (node (ref "C9") (pin "2") (pinfunction "2_2") (pintype "passive"))
      (node (ref "IC1") (pin "F6") (pinfunction "DGND_USB_F6") (pintype "passive"))
      (node (ref "IC1") (pin "F7") (pinfunction "DGND2/LCD_GND_F7") (pintype "passive"))
      (node (ref "IC1") (pin "G6") (pinfunction "DGND1_G6") (pintype "passive"))
      (node (ref "IC1") (pin "H14") (pinfunction "DGND_H14") (pintype "passive"))
      (node (ref "IC2") (pin "4") (pinfunction "V-_4") (pintype "power_in"))
      (node (ref "IC5") (pin "1") (pinfunction "GND_1") (pintype "power_in"))
      (node (ref "IC5") (pin "5") (pinfunction "SDO/DNC/A_5") (pintype "input"))
      (node (ref "IC5") (pin "7") (pinfunction "GND_7") (pintype "power_in"))
      (node (ref "IC6") (pin "2") (pinfunction "VSS_2") (pintype "power_in"))
      (node (ref "IC6") (pin "9") (pinfunction "GND_9") (pintype "power_in"))
      (node (ref "IC7") (pin "5") (pinfunction "LDAC_5") (pintype "input"))
      (node (ref "IC7") (pin "7") (pinfunction "VSS_7") (pintype "power_in"))
      (node (ref "IC8") (pin "1") (pinfunction "A0_1") (pintype "input"))
      (node (ref "IC8") (pin "2") (pinfunction "A1_2") (pintype "input"))
      (node (ref "IC8") (pin "3") (pinfunction "A2_3") (pintype "input"))
      (node (ref "IC8") (pin "4") (pinfunction "GND_4") (pintype "power_in"))
      (node (ref "JP1") (pin "2") (pinfunction "2_2") (pintype "passive"))
      (node (ref "JP4") (pin "6") (pinfunction "6_6") (pintype "passive"))
      (node (ref "JP5") (pin "6") (pinfunction "6_6") (pintype "passive"))
      (node (ref "PCB1") (pin "14") (pinfunction "GND_14") (pintype "power_in"))
      (node (ref "PCB1") (pin "20") (pinfunction "GND_20") (pintype "power_in"))
      (node (ref "PCB1") (pin "25") (pinfunction "GND_25") (pintype "power_in"))
      (node (ref "PCB1") (pin "30") (pinfunction "GND_30") (pintype "power_in"))
      (node (ref "PCB1") (pin "34") (pinfunction "GND_34") (pintype "power_in"))
      (node (ref "PCB1") (pin "39") (pinfunction "GND_39") (pintype "power_in"))
      (node (ref "PCB1") (pin "6") (pinfunction "GND_6") (pintype "power_in"))
      (node (ref "PCB1") (pin "9") (pinfunction "GND_9") (pintype "power_in"))
      (node (ref "PCB1") (pin "PE_BL") (pinfunction "BL_PE_BL") (pintype "bidirectional"))
      (node (ref "PCB1") (pin "PE_BR") (pinfunction "BR_PE_BR") (pintype "bidirectional"))
      (node (ref "PCB1") (pin "PE_TL") (pinfunction "TL_PE_TL") (pintype "bidirectional"))
      (node (ref "PCB1") (pin "PE_TR") (pinfunction "TR_PE_TR") (pintype "bidirectional"))
      (node (ref "R3") (pin "1") (pinfunction "1_1") (pintype "passive"))
      (node (ref "S1") (pin "5") (pinfunction "SH_5") (pintype "passive"))
      (node (ref "S2") (pin "1") (pinfunction "1.1_1") (pintype "passive"))
      (node (ref "S2") (pin "2") (pinfunction "1.2_2") (pintype "passive"))
      (node (ref "S2") (pin "5") (pinfunction "SH_5") (pintype "passive"))
      (node (ref "T1") (pin "2") (pinfunction "S_2") (pintype "passive"))
      (node (ref "TP10") (pin "TP") (pinfunction "TP_TP") (pintype "input"))
      (node (ref "X1") (pin "A5") (pinfunction "A5_A5") (pintype "passive"))
    )
    (net (code "29") (name "GNDA") (class "Default")
      (node (ref "C19") (pin "2") (pinfunction "2_2") (pintype "passive"))
      (node (ref "C20") (pin "1") (pinfunction "1_1") (pintype "passive"))
      (node (ref "C22") (pin "2") (pinfunction "2_2") (pintype "passive"))
      (node (ref "IC1") (pin "K10") (pinfunction "AGND_REF_K10") (pintype "passive"))
      (node (ref "IC1") (pin "K9") (pinfunction "AGND_RX/AGND_TX_K9") (pintype "passive"))
      (node (ref "IC1") (pin "P14") (pinfunction "AGND_CTOUCH_P14") (pintype "passive"))
      (node (ref "IC3") (pin "5") (pinfunction "-V_5") (pintype "power_in"))
      (node (ref "IC4") (pin "4") (pinfunction "V-_4") (pintype "power_in"))
      (node (ref "R19") (pin "1") (pinfunction "1_1") (pintype "passive"))
      (node (ref "R23") (pin "1") (pinfunction "1_1") (pintype "passive"))
      (node (ref "X1") (pin "A10") (pinfunction "A10_A10") (pintype "passive"))
      (node (ref "X1") (pin "A14") (pinfunction "A14_A14") (pintype "passive"))
      (node (ref "X1") (pin "A16") (pinfunction "A16_A16") (pintype "passive"))
      (node (ref "X1") (pin "B1") (pinfunction "B1_B1") (pintype "passive"))
      (node (ref "X1") (pin "B10") (pinfunction "B10_B10") (pintype "passive"))
      (node (ref "X1") (pin "B12") (pinfunction "B12_B12") (pintype "passive"))
      (node (ref "X1") (pin "B17") (pinfunction "B17_B17") (pintype "passive"))
      (node (ref "X1") (pin "B4") (pinfunction "B4_B4") (pintype "passive"))
      (node (ref "X1") (pin "B6") (pinfunction "B6_B6") (pintype "passive"))
    )
    (net (code "30") (name "GPIO0") (class "Default")
      (node (ref "IC1") (pin "A13") (pinfunction "P2.10/S23_A13") (pintype "passive"))
      (node (ref "JP5") (pin "2") (pinfunction "2_2") (pintype "passive"))
    )
    (net (code "31") (name "GPIO1") (class "Default")
      (node (ref "IC1") (pin "A14") (pinfunction "P2.9/S22_A14") (pintype "passive"))
      (node (ref "JP5") (pin "3") (pinfunction "3_3") (pintype "passive"))
    )
    (net (code "32") (name "H1") (class "Default")
      (node (ref "T2") (pin "3") (pinfunction "D_3") (pintype "passive"))
      (node (ref "X1") (pin "B5") (pinfunction "B5_B5") (pintype "passive"))
    )
    (net (code "33") (name "H2") (class "Default")
      (node (ref "X1") (pin "B13") (pinfunction "B13_B13") (pintype "passive"))
    )
    (net (code "34") (name "HF1") (class "Default")
      (node (ref "C4") (pin "2") (pinfunction "2_2") (pintype "passive"))
      (node (ref "IC1") (pin "D1") (pinfunction "HF_XTAL1_D1") (pintype "passive"))
      (node (ref "Q1") (pin "3") (pinfunction "2_3") (pintype "passive"))
    )
    (net (code "35") (name "HF2") (class "Default")
      (node (ref "C3") (pin "2") (pinfunction "2_2") (pintype "passive"))
      (node (ref "IC1") (pin "C1") (pinfunction "HF_XTAL2_C1") (pintype "passive"))
      (node (ref "Q1") (pin "1") (pinfunction "1_1") (pintype "passive"))
    )
    (net (code "36") (name "HT_A") (class "Default")
      (node (ref "X1") (pin "A18") (pinfunction "A18_A18") (pintype "passive"))
    )
    (net (code "37") (name "HT_B") (class "Default")
      (node (ref "X1") (pin "A11") (pinfunction "A11_A11") (pintype "passive"))
    )
    (net (code "38") (name "HZ_EN") (class "Default")
      (node (ref "R5") (pin "1") (pinfunction "1_1") (pintype "passive"))
      (node (ref "R6") (pin "1") (pinfunction "1_1") (pintype "passive"))
    )
    (net (code "39") (name "I_SOLL") (class "Default")
      (node (ref "IC7") (pin "8") (pinfunction "VOUT_8") (pintype "output"))
      (node (ref "R4") (pin "1") (pinfunction "1_1") (pintype "passive"))
    )
    (net (code "40") (name "MOSI") (class "Default")
      (node (ref "IC1") (pin "F15") (pinfunction "P3.2/SPI0_MOSI_F15") (pintype "passive"))
      (node (ref "IC6") (pin "10") (pinfunction "SDI_10") (pintype "input"))
      (node (ref "IC7") (pin "4") (pinfunction "SDI_4") (pintype "input"))
    )
    (net (code "41") (name "Net-(C15-Pad1)") (class "Default")
      (node (ref "C15") (pin "1") (pinfunction "1_1") (pintype "passive"))
      (node (ref "R13") (pin "2") (pinfunction "2_2") (pintype "passive"))
    )
    (net (code "42") (name "Net-(C16-Pad1)") (class "Default")
      (node (ref "C16") (pin "1") (pinfunction "1_1") (pintype "passive"))
      (node (ref "R14") (pin "2") (pinfunction "2_2") (pintype "passive"))
    )
    (net (code "43") (name "Net-(C17-Pad2)") (class "Default")
      (node (ref "C17") (pin "2") (pinfunction "2_2") (pintype "passive"))
      (node (ref "R16") (pin "2") (pinfunction "2_2") (pintype "passive"))
    )
    (net (code "44") (name "Net-(C18-Pad2)") (class "Default")
      (node (ref "C18") (pin "2") (pinfunction "2_2") (pintype "passive"))
      (node (ref "R15") (pin "2") (pinfunction "2_2") (pintype "passive"))
    )
    (net (code "45") (name "Net-(IC1A-AVDD_RX{slash}AVDD_TX)") (class "Default")
      (node (ref "C11") (pin "1") (pinfunction "1_1") (pintype "passive"))
      (node (ref "IC1") (pin "R4") (pinfunction "AVDD_RX/AVDD_TX_R4") (pintype "passive"))
    )
    (net (code "46") (name "Net-(IC1A-DVDD)") (class "Default")
      (node (ref "C10") (pin "1") (pinfunction "1_1") (pintype "passive"))
      (node (ref "IC1") (pin "K1") (pinfunction "DVDD_K1") (pintype "passive"))
    )
    (net (code "47") (name "Net-(IC1A-RCAL_1)") (class "Default")
      (node (ref "IC1") (pin "P5") (pinfunction "RCAL_1_P5") (pintype "passive"))
      (node (ref "R8") (pin "2") (pinfunction "2_2") (pintype "passive"))
    )
    (net (code "48") (name "Net-(IC1A-RCAL_2)") (class "Default")
      (node (ref "IC1") (pin "R5") (pinfunction "RCAL_2_R5") (pintype "passive"))
      (node (ref "R8") (pin "1") (pinfunction "1_1") (pintype "passive"))
    )
    (net (code "49") (name "Net-(IC1A-TIA_I)") (class "Default")
      (node (ref "IC1") (pin "P11") (pinfunction "TIA_I_P11") (pintype "passive"))
      (node (ref "IC6") (pin "4") (pinfunction "W_4") (pintype "passive"))
      (node (ref "R9") (pin "2") (pinfunction "2_2") (pintype "passive"))
    )
    (net (code "50") (name "Net-(IC1A-TIA_O)") (class "Default")
      (node (ref "IC1") (pin "R11") (pinfunction "TIA_O_R11") (pintype "passive"))
      (node (ref "IC6") (pin "3") (pinfunction "A_3") (pintype "passive"))
      (node (ref "R9") (pin "1") (pinfunction "1_1") (pintype "passive"))
    )
    (net (code "51") (name "Net-(IC1A-VREF)") (class "Default")
      (node (ref "C9") (pin "1") (pinfunction "1_1") (pintype "passive"))
      (node (ref "IC1") (pin "R10") (pinfunction "VREF_R10") (pintype "passive"))
    )
    (net (code "52") (name "Net-(IC1B-P3.6{slash}UTX{slash}TOUTB{slash}SPI1_MOSI)") (class "Default")
      (node (ref "IC1") (pin "G15") (pinfunction "P3.6/UTX/TOUTB/SPI1_MOSI_G15") (pintype "passive"))
      (node (ref "SJ2") (pin "1") (pinfunction "1_1") (pintype "passive"))
    )
    (net (code "53") (name "Net-(IC1B-P3.7{slash}URX{slash}TOUTC{slash}SPI1_CS)") (class "Default")
      (node (ref "IC1") (pin "J10") (pinfunction "P3.7/URX/TOUTC/SPI1_CS_J10") (pintype "passive"))
      (node (ref "SJ1") (pin "1") (pinfunction "1_1") (pintype "passive"))
    )
    (net (code "54") (name "Net-(IC2-+IN)") (class "Default")
      (node (ref "C7") (pin "1") (pinfunction "1_1") (pintype "passive"))
      (node (ref "IC2") (pin "3") (pinfunction "+IN_3") (pintype "input"))
      (node (ref "R4") (pin "2") (pinfunction "2_2") (pintype "passive"))
      (node (ref "T1") (pin "3") (pinfunction "D_3") (pintype "passive"))
    )
    (net (code "55") (name "Net-(IC2--IN)") (class "Default")
      (node (ref "C5") (pin "2") (pinfunction "2_2") (pintype "passive"))
      (node (ref "IC2") (pin "2") (pinfunction "-IN_2") (pintype "input"))
      (node (ref "R2") (pin "1") (pinfunction "1_1") (pintype "passive"))
    )
    (net (code "56") (name "Net-(IC2-OUT)") (class "Default")
      (node (ref "C5") (pin "1") (pinfunction "1_1") (pintype "passive"))
      (node (ref "IC2") (pin "6") (pinfunction "OUT_6") (pintype "output"))
      (node (ref "R1") (pin "1") (pinfunction "1_1") (pintype "passive"))
    )
    (net (code "57") (name "Net-(IC3-+)") (class "Default")
      (node (ref "C15") (pin "2") (pinfunction "2_2") (pintype "passive"))
      (node (ref "IC3") (pin "1") (pinfunction "+_1") (pintype "input"))
      (node (ref "R11") (pin "1") (pinfunction "1_1") (pintype "passive"))
    )
    (net (code "58") (name "Net-(IC3--)") (class "Default")
      (node (ref "C16") (pin "2") (pinfunction "2_2") (pintype "passive"))
      (node (ref "IC3") (pin "4") (pinfunction "-_4") (pintype "input"))
      (node (ref "R12") (pin "1") (pinfunction "1_1") (pintype "passive"))
    )
    (net (code "59") (name "Net-(IC3-RG-Pad2)") (class "Default")
      (node (ref "IC3") (pin "2") (pinfunction "RG_2") (pintype "passive"))
      (node (ref "R10") (pin "2") (pinfunction "2_2") (pintype "passive"))
    )
    (net (code "60") (name "Net-(IC3-RG-Pad3)") (class "Default")
      (node (ref "IC3") (pin "3") (pinfunction "RG_3") (pintype "passive"))
      (node (ref "R10") (pin "1") (pinfunction "1_1") (pintype "passive"))
    )
    (net (code "61") (name "Net-(IC4A-+IN)") (class "Default")
      (node (ref "IC4") (pin "3") (pinfunction "+IN_3") (pintype "input"))
      (node (ref "R17") (pin "1") (pinfunction "1_1") (pintype "passive"))
      (node (ref "R19") (pin "2") (pinfunction "2_2") (pintype "passive"))
    )
    (net (code "62") (name "Net-(IC4B-+IN)") (class "Default")
      (node (ref "IC4") (pin "5") (pinfunction "+IN_5") (pintype "input"))
      (node (ref "R22") (pin "1") (pinfunction "1_1") (pintype "passive"))
      (node (ref "R23") (pin "2") (pinfunction "2_2") (pintype "passive"))
    )
    (net (code "63") (name "Net-(IC4B--IN)") (class "Default")
      (node (ref "C20") (pin "2") (pinfunction "2_2") (pintype "passive"))
      (node (ref "IC4") (pin "6") (pinfunction "-IN_6") (pintype "input"))
      (node (ref "R20") (pin "2") (pinfunction "2_2") (pintype "passive"))
      (node (ref "R21") (pin "1") (pinfunction "1_1") (pintype "passive"))
    )
    (net (code "64") (name "Net-(IC6-EXT_CAP)") (class "Default")
      (node (ref "C29") (pin "1") (pinfunction "1_1") (pintype "passive"))
      (node (ref "IC6") (pin "7") (pinfunction "EXT_CAP_7") (pintype "passive"))
    )
    (net (code "65") (name "Net-(IC8-SCL)") (class "Default")
      (node (ref "IC8") (pin "6") (pinfunction "SCL_6") (pintype "input"))
      (node (ref "PCB1") (pin "28") (pinfunction "ID_SC_28") (pintype "bidirectional"))
    )
    (net (code "66") (name "Net-(IC8-SDA)") (class "Default")
      (node (ref "IC8") (pin "5") (pinfunction "SDA_5") (pintype "bidirectional"))
      (node (ref "PCB1") (pin "27") (pinfunction "ID_SD_27") (pintype "bidirectional"))
    )
    (net (code "67") (name "Net-(IC8-WP)") (class "Default")
      (node (ref "IC8") (pin "7") (pinfunction "WP_7") (pintype "input"))
      (node (ref "R27") (pin "1") (pinfunction "1_1") (pintype "passive"))
      (node (ref "TP9") (pin "TP") (pinfunction "TP_TP") (pintype "input"))
    )
    (net (code "68") (name "Net-(PCB1-GPIO20)") (class "Default")
      (node (ref "PCB1") (pin "38") (pinfunction "GPIO20_38") (pintype "bidirectional"))
      (node (ref "SJ3") (pin "1") (pinfunction "1_1") (pintype "passive"))
    )
    (net (code "69") (name "Net-(PCB1-GPIO21)") (class "Default")
      (node (ref "PCB1") (pin "40") (pinfunction "GPIO21_40") (pintype "bidirectional"))
      (node (ref "SJ4") (pin "1") (pinfunction "1_1") (pintype "passive"))
    )
    (net (code "70") (name "Net-(S1-2.1)") (class "Default")
      (node (ref "R7") (pin "1") (pinfunction "1_1") (pintype "passive"))
      (node (ref "S1") (pin "3") (pinfunction "2.1_3") (pintype "passive"))
      (node (ref "S1") (pin "4") (pinfunction "2.2_4") (pintype "passive"))
    )
    (net (code "71") (name "Net-(T1-G)") (class "Default")
      (node (ref "R5") (pin "2") (pinfunction "2_2") (pintype "passive"))
      (node (ref "T1") (pin "1") (pinfunction "G_1") (pintype "passive"))
    )
    (net (code "72") (name "Net-(T2-G)") (class "Default")
      (node (ref "R1") (pin "2") (pinfunction "2_2") (pintype "passive"))
      (node (ref "T2") (pin "1") (pinfunction "G_1") (pintype "passive"))
    )
    (net (code "73") (name "Net-(T2-S)") (class "Default")
      (node (ref "R2") (pin "2") (pinfunction "2_2") (pintype "passive"))
      (node (ref "R3") (pin "2") (pinfunction "2_2") (pintype "passive"))
      (node (ref "T2") (pin "2") (pinfunction "S_2") (pintype "passive"))
    )
    (net (code "74") (name "PCS") (class "Default")
      (node (ref "IC1") (pin "K15") (pinfunction "P0.0/CAPT_A_K15") (pintype "passive"))
      (node (ref "IC6") (pin "12") (pinfunction "SYNC_12") (pintype "input"))
    )
    (net (code "75") (name "RE1") (class "Default")
      (node (ref "IC1") (pin "R8") (pinfunction "AFE_5_R8") (pintype "passive"))
      (node (ref "SJ7") (pin "2") (pinfunction "2_2") (pintype "passive"))
      (node (ref "X1") (pin "B8") (pinfunction "B8_B8") (pintype "passive"))
    )
    (net (code "76") (name "RE1_E") (class "Default")
      (node (ref "TP2") (pin "A") (pinfunction "P$1_A") (pintype "passive"))
      (node (ref "TP2") (pin "B") (pinfunction "P$2_B") (pintype "passive"))
      (node (ref "X2") (pin "B8") (pinfunction "B8_B8") (pintype "passive"))
    )
    (net (code "77") (name "RE2") (class "Default")
      (node (ref "IC1") (pin "P8") (pinfunction "AFE_6_P8") (pintype "passive"))
      (node (ref "X1") (pin "B11") (pinfunction "B11_B11") (pintype "passive"))
    )
    (net (code "78") (name "RE2_E") (class "Default")
      (node (ref "TP4") (pin "A") (pinfunction "P$1_A") (pintype "passive"))
      (node (ref "TP4") (pin "B") (pinfunction "P$2_B") (pintype "passive"))
      (node (ref "X2") (pin "B11") (pinfunction "B11_B11") (pintype "passive"))
    )
    (net (code "79") (name "RE3") (class "Default")
      (node (ref "IC1") (pin "P7") (pinfunction "AFE_4_P7") (pintype "passive"))
      (node (ref "TP8") (pin "A") (pinfunction "P$1_A") (pintype "passive"))
      (node (ref "TP8") (pin "B") (pinfunction "P$2_B") (pintype "passive"))
    )
    (net (code "80") (name "REF_E") (class "Default")
      (node (ref "IC1") (pin "R12") (pinfunction "REF_EXCITE_R12") (pintype "passive"))
    )
    (net (code "81") (name "RST") (class "Default")
      (node (ref "IC1") (pin "K8") (pinfunction "RESETX_K8") (pintype "passive"))
      (node (ref "JP1") (pin "1") (pinfunction "1_1") (pintype "passive"))
      (node (ref "S2") (pin "3") (pinfunction "2.1_3") (pintype "passive"))
      (node (ref "S2") (pin "4") (pinfunction "2.2_4") (pintype "passive"))
      (node (ref "SJ3") (pin "2") (pinfunction "2_2") (pintype "passive"))
    )
    (net (code "82") (name "RTC1") (class "Default")
      (node (ref "C2") (pin "2") (pinfunction "2_2") (pintype "passive"))
      (node (ref "IC1") (pin "P1") (pinfunction "LF_XTAL1_P1") (pintype "passive"))
      (node (ref "Q2") (pin "2") (pinfunction "2_2") (pintype "passive"))
    )
    (net (code "83") (name "RTC2") (class "Default")
      (node (ref "C1") (pin "2") (pinfunction "2_2") (pintype "passive"))
      (node (ref "IC1") (pin "N1") (pinfunction "LF_XTAL2_N1") (pintype "passive"))
      (node (ref "Q2") (pin "1") (pinfunction "1_1") (pintype "passive"))
    )
    (net (code "84") (name "RX") (class "Default")
      (node (ref "PCB1") (pin "8") (pinfunction "TXD0/GPIO14_8") (pintype "bidirectional"))
      (node (ref "SJ1") (pin "2") (pinfunction "2_2") (pintype "passive"))
    )
    (net (code "85") (name "SCL") (class "Default")
      (node (ref "IC1") (pin "G10") (pinfunction "P3.4/I2CSCL/SPI1_SCLK_G10") (pintype "passive"))
      (node (ref "IC5") (pin "4") (pinfunction "SCK/SCL_4") (pintype "bidirectional"))
      (node (ref "JP4") (pin "2") (pinfunction "2_2") (pintype "passive"))
      (node (ref "PCB1") (pin "5") (pinfunction "GPIO03/SCL1_5") (pintype "bidirectional"))
      (node (ref "R26") (pin "1") (pinfunction "1_1") (pintype "passive"))
      (node (ref "X1") (pin "A4") (pinfunction "A4_A4") (pintype "passive"))
    )
    (net (code "86") (name "SCLK") (class "Default")
      (node (ref "IC1") (pin "F14") (pinfunction "P3.0/SPI0_SCLK_F14") (pintype "passive"))
      (node (ref "IC6") (pin "11") (pinfunction "SCLK_11") (pintype "input"))
      (node (ref "IC7") (pin "3") (pinfunction "SCK_3") (pintype "input"))
    )
    (net (code "87") (name "SCS") (class "Default")
      (node (ref "IC1") (pin "F10") (pinfunction "P3.3/SPI0_CS_F10") (pintype "passive"))
      (node (ref "IC7") (pin "2") (pinfunction "CS_2") (pintype "input"))
    )
    (net (code "88") (name "SDA") (class "Default")
      (node (ref "IC1") (pin "H10") (pinfunction "P3.5/I2CSD/SPI1_MISO_H10") (pintype "passive"))
      (node (ref "IC5") (pin "3") (pinfunction "SDI/SDO/SDA_3") (pintype "bidirectional"))
      (node (ref "JP4") (pin "3") (pinfunction "3_3") (pintype "passive"))
      (node (ref "PCB1") (pin "3") (pinfunction "GPIO02/SDA1_3") (pintype "bidirectional"))
      (node (ref "R25") (pin "1") (pinfunction "1_1") (pintype "passive"))
      (node (ref "X1") (pin "A3") (pinfunction "A3_A3") (pintype "passive"))
    )
    (net (code "89") (name "SOURCE1") (class "Default")
      (node (ref "X1") (pin "A13") (pinfunction "A13_A13") (pintype "passive"))
    )
    (net (code "90") (name "SOURCE2") (class "Default")
      (node (ref "X1") (pin "A9") (pinfunction "A9_A9") (pintype "passive"))
    )
    (net (code "91") (name "SUBSTRAT") (class "Default")
      (node (ref "X1") (pin "A17") (pinfunction "A17_A17") (pintype "passive"))
    )
    (net (code "92") (name "SWCLK") (class "Default")
      (node (ref "IC1") (pin "H2") (pinfunction "TCK-SWCLK/P0.9_H2") (pintype "passive"))
      (node (ref "JP1") (pin "5") (pinfunction "5_5") (pintype "passive"))
    )
    (net (code "93") (name "SWIO") (class "Default")
      (node (ref "IC1") (pin "H1") (pinfunction "TMS-SWDIO/P0.8_H1") (pintype "passive"))
      (node (ref "JP1") (pin "3") (pinfunction "3_3") (pintype "passive"))
    )
    (net (code "94") (name "T1") (class "Default")
      (node (ref "IC4") (pin "2") (pinfunction "-IN_2") (pintype "input"))
      (node (ref "R18") (pin "1") (pinfunction "1_1") (pintype "passive"))
      (node (ref "X1") (pin "B2") (pinfunction "B2_B2") (pintype "passive"))
    )
    (net (code "95") (name "T1_E") (class "Default")
      (node (ref "TP5") (pin "A") (pinfunction "P$1_A") (pintype "passive"))
      (node (ref "TP5") (pin "B") (pinfunction "P$2_B") (pintype "passive"))
      (node (ref "X2") (pin "B2") (pinfunction "B2_B2") (pintype "passive"))
    )
    (net (code "96") (name "T2") (class "Default")
      (node (ref "IC4") (pin "1") (pinfunction "OUT_1") (pintype "output"))
      (node (ref "R20") (pin "1") (pinfunction "1_1") (pintype "passive"))
      (node (ref "X1") (pin "B3") (pinfunction "B3_B3") (pintype "passive"))
    )
    (net (code "97") (name "T2_E") (class "Default")
      (node (ref "TP6") (pin "A") (pinfunction "P$1_A") (pintype "passive"))
      (node (ref "TP6") (pin "B") (pinfunction "P$2_B") (pintype "passive"))
      (node (ref "X2") (pin "B3") (pinfunction "B3_B3") (pintype "passive"))
    )
    (net (code "98") (name "TX") (class "Default")
      (node (ref "PCB1") (pin "10") (pinfunction "RXD0/GPIO15_10") (pintype "bidirectional"))
      (node (ref "SJ2") (pin "2") (pinfunction "2_2") (pintype "passive"))
    )
    (net (code "99") (name "V+") (class "Default")
      (node (ref "C8") (pin "1") (pinfunction "1_1") (pintype "passive"))
      (node (ref "IC1") (pin "P10") (pinfunction "VBIAS_P10") (pintype "passive"))
      (node (ref "IC3") (pin "6") (pinfunction "REF_6") (pintype "passive"))
      (node (ref "R11") (pin "2") (pinfunction "2_2") (pintype "passive"))
      (node (ref "R12") (pin "2") (pinfunction "2_2") (pintype "passive"))
    )
    (net (code "100") (name "unconnected-(IC1A-DNC-PadA1)") (class "Default")
      (node (ref "IC1") (pin "A1") (pinfunction "DNC_A1") (pintype "passive"))
    )
    (net (code "101") (name "unconnected-(IC1A-FFLX-PadF9)") (class "Default")
      (node (ref "IC1") (pin "F9") (pinfunction "FFLX_F9") (pintype "passive"))
    )
    (net (code "102") (name "unconnected-(IC1A-TRACE0-PadM14)") (class "Default")
      (node (ref "IC1") (pin "M14") (pinfunction "TRACE0_M14") (pintype "passive"))
    )
    (net (code "103") (name "unconnected-(IC1A-TRACE1-PadN15)") (class "Default")
      (node (ref "IC1") (pin "N15") (pinfunction "TRACE1_N15") (pintype "passive"))
    )
    (net (code "104") (name "unconnected-(IC1A-TRACE2-PadN14)") (class "Default")
      (node (ref "IC1") (pin "N14") (pinfunction "TRACE2_N14") (pintype "passive"))
    )
    (net (code "105") (name "unconnected-(IC1A-TRACE3-PadP15)") (class "Default")
      (node (ref "IC1") (pin "P15") (pinfunction "TRACE3_P15") (pintype "passive"))
    )
    (net (code "106") (name "unconnected-(IC1A-TRACECLK-PadM15)") (class "Default")
      (node (ref "IC1") (pin "M15") (pinfunction "TRACECLK_M15") (pintype "passive"))
    )
    (net (code "107") (name "unconnected-(IC1A-TRST-PadR15)") (class "Default")
      (node (ref "IC1") (pin "R15") (pinfunction "TRST_R15") (pintype "passive"))
    )
    (net (code "108") (name "unconnected-(IC1A-USB_DM-PadF1)") (class "Default")
      (node (ref "IC1") (pin "F1") (pinfunction "USB_DM_F1") (pintype "passive"))
    )
    (net (code "109") (name "unconnected-(IC1A-USB_DP-PadG1)") (class "Default")
      (node (ref "IC1") (pin "G1") (pinfunction "USB_DP_G1") (pintype "passive"))
    )
    (net (code "110") (name "unconnected-(IC1A-VBACK-PadM1)") (class "Default")
      (node (ref "IC1") (pin "M1") (pinfunction "VBACK_M1") (pintype "passive"))
    )
    (net (code "111") (name "unconnected-(IC1A-VBUS-PadG2)") (class "Default")
      (node (ref "IC1") (pin "G2") (pinfunction "VBUS_G2") (pintype "passive"))
    )
    (net (code "112") (name "unconnected-(IC1A-VLCD_FLY1-PadE2)") (class "Default")
      (node (ref "IC1") (pin "E2") (pinfunction "VLCD_FLY1_E2") (pintype "passive"))
    )
    (net (code "113") (name "unconnected-(IC1A-VLCD_FLY2-PadF2)") (class "Default")
      (node (ref "IC1") (pin "F2") (pinfunction "VLCD_FLY2_F2") (pintype "passive"))
    )
    (net (code "114") (name "unconnected-(IC1A-VUSB-PadE1)") (class "Default")
      (node (ref "IC1") (pin "E1") (pinfunction "VUSB_E1") (pintype "passive"))
    )
    (net (code "115") (name "unconnected-(IC1A-V_LCD_13-PadC2)") (class "Default")
      (node (ref "IC1") (pin "C2") (pinfunction "V_LCD_13_C2") (pintype "passive"))
    )
    (net (code "116") (name "unconnected-(IC1A-V_LCD_23-PadB1)") (class "Default")
      (node (ref "IC1") (pin "B1") (pinfunction "V_LCD_23_B1") (pintype "passive"))
    )
    (net (code "117") (name "unconnected-(IC1B-P0.1{slash}CAPT_B-PadJ15)") (class "Default")
      (node (ref "IC1") (pin "J15") (pinfunction "P0.1/CAPT_B_J15") (pintype "passive"))
    )
    (net (code "118") (name "unconnected-(IC1B-P0.2{slash}CAPT_C-PadL15)") (class "Default")
      (node (ref "IC1") (pin "L15") (pinfunction "P0.2/CAPT_C_L15") (pintype "passive"))
    )
    (net (code "119") (name "unconnected-(IC1B-P0.3{slash}CAPT_D-PadK14)") (class "Default")
      (node (ref "IC1") (pin "K14") (pinfunction "P0.3/CAPT_D_K14") (pintype "passive"))
    )
    (net (code "120") (name "unconnected-(IC1B-P0.4{slash}CAPT_E-PadJ14)") (class "Default")
      (node (ref "IC1") (pin "J14") (pinfunction "P0.4/CAPT_E_J14") (pintype "passive"))
    )
    (net (code "121") (name "unconnected-(IC1B-P0.5{slash}CAPT_F-PadL14)") (class "Default")
      (node (ref "IC1") (pin "L14") (pinfunction "P0.5/CAPT_F_L14") (pintype "passive"))
    )
    (net (code "122") (name "unconnected-(IC1B-P0.10{slash}TOUTC-PadR2)") (class "Default")
      (node (ref "IC1") (pin "R2") (pinfunction "P0.10/TOUTC_R2") (pintype "passive"))
    )
    (net (code "123") (name "unconnected-(IC1B-P0.11-PadK2)") (class "Default")
      (node (ref "IC1") (pin "K2") (pinfunction "P0.11_K2") (pintype "passive"))
    )
    (net (code "124") (name "unconnected-(IC1B-P0.12{slash}SPIH_SCLK-PadR3)") (class "Default")
      (node (ref "IC1") (pin "R3") (pinfunction "P0.12/SPIH_SCLK_R3") (pintype "passive"))
    )
    (net (code "125") (name "unconnected-(IC1B-P0.13{slash}SPIH_MISO-PadP2)") (class "Default")
      (node (ref "IC1") (pin "P2") (pinfunction "P0.13/SPIH_MISO_P2") (pintype "passive"))
    )
    (net (code "126") (name "unconnected-(IC1B-P0.14{slash}SPIH_MOSI-PadP3)") (class "Default")
      (node (ref "IC1") (pin "P3") (pinfunction "P0.14/SPIH_MOSI_P3") (pintype "passive"))
    )
    (net (code "127") (name "unconnected-(IC1B-P0.15{slash}SPIH_CS-PadM2)") (class "Default")
      (node (ref "IC1") (pin "M2") (pinfunction "P0.15/SPIH_CS_M2") (pintype "passive"))
    )
    (net (code "128") (name "unconnected-(IC1B-P1.0{slash}S3{slash}D0{slash}SCL-PadA5)") (class "Default")
      (node (ref "IC1") (pin "A5") (pinfunction "P1.0/S3/D0/SCL_A5") (pintype "passive"))
    )
    (net (code "129") (name "unconnected-(IC1B-P1.1{slash}S4{slash}D1{slash}DOUT-PadB5)") (class "Default")
      (node (ref "IC1") (pin "B5") (pinfunction "P1.1/S4/D1/DOUT_B5") (pintype "passive"))
    )
    (net (code "130") (name "unconnected-(IC1B-P1.2{slash}S5{slash}D2{slash}DIN-PadA6)") (class "Default")
      (node (ref "IC1") (pin "A6") (pinfunction "P1.2/S5/D2/DIN_A6") (pintype "passive"))
    )
    (net (code "131") (name "unconnected-(IC1B-P1.3{slash}S6{slash}D3-PadB6)") (class "Default")
      (node (ref "IC1") (pin "B6") (pinfunction "P1.3/S6/D3_B6") (pintype "passive"))
    )
    (net (code "132") (name "unconnected-(IC1B-P1.4{slash}S7{slash}D4-PadA7)") (class "Default")
      (node (ref "IC1") (pin "A7") (pinfunction "P1.4/S7/D4_A7") (pintype "passive"))
    )
    (net (code "133") (name "unconnected-(IC1B-P1.5{slash}S8{slash}D5-PadB7)") (class "Default")
      (node (ref "IC1") (pin "B7") (pinfunction "P1.5/S8/D5_B7") (pintype "passive"))
    )
    (net (code "134") (name "unconnected-(IC1B-P1.6{slash}S9{slash}D6-PadA8)") (class "Default")
      (node (ref "IC1") (pin "A8") (pinfunction "P1.6/S9/D6_A8") (pintype "passive"))
    )
    (net (code "135") (name "unconnected-(IC1B-P1.7{slash}S10{slash}D7-PadB8)") (class "Default")
      (node (ref "IC1") (pin "B8") (pinfunction "P1.7/S10/D7_B8") (pintype "passive"))
    )
    (net (code "136") (name "unconnected-(IC1B-P1.8{slash}S11{slash}D8-PadA9)") (class "Default")
      (node (ref "IC1") (pin "A9") (pinfunction "P1.8/S11/D8_A9") (pintype "passive"))
    )
    (net (code "137") (name "unconnected-(IC1B-P1.9{slash}S12{slash}D9-PadB9)") (class "Default")
      (node (ref "IC1") (pin "B9") (pinfunction "P1.9/S12/D9_B9") (pintype "passive"))
    )
    (net (code "138") (name "unconnected-(IC1B-P1.10{slash}S13{slash}D10-PadA10)") (class "Default")
      (node (ref "IC1") (pin "A10") (pinfunction "P1.10/S13/D10_A10") (pintype "passive"))
    )
    (net (code "139") (name "unconnected-(IC1B-P1.11{slash}S14{slash}D11-PadB10)") (class "Default")
      (node (ref "IC1") (pin "B10") (pinfunction "P1.11/S14/D11_B10") (pintype "passive"))
    )
    (net (code "140") (name "unconnected-(IC1B-P1.12{slash}S15{slash}D12-PadA11)") (class "Default")
      (node (ref "IC1") (pin "A11") (pinfunction "P1.12/S15/D12_A11") (pintype "passive"))
    )
    (net (code "141") (name "unconnected-(IC1B-P1.13{slash}S16{slash}D13-PadB11)") (class "Default")
      (node (ref "IC1") (pin "B11") (pinfunction "P1.13/S16/D13_B11") (pintype "passive"))
    )
    (net (code "142") (name "unconnected-(IC1B-P1.14{slash}S17{slash}D14-PadA12)") (class "Default")
      (node (ref "IC1") (pin "A12") (pinfunction "P1.14/S17/D14_A12") (pintype "passive"))
    )
    (net (code "143") (name "unconnected-(IC1B-P1.15{slash}S18{slash}D15-PadB12)") (class "Default")
      (node (ref "IC1") (pin "B12") (pinfunction "P1.15/S18/D15_B12") (pintype "passive"))
    )
    (net (code "144") (name "unconnected-(IC1B-P2.0{slash}COM0-PadB2)") (class "Default")
      (node (ref "IC1") (pin "B2") (pinfunction "P2.0/COM0_B2") (pintype "passive"))
    )
    (net (code "145") (name "unconnected-(IC1B-P2.1{slash}COM1{slash}RESX-PadA2)") (class "Default")
      (node (ref "IC1") (pin "A2") (pinfunction "P2.1/COM1/RESX_A2") (pintype "passive"))
    )
    (net (code "146") (name "unconnected-(IC1B-P2.2{slash}COM2{slash}CSX-PadB3)") (class "Default")
      (node (ref "IC1") (pin "B3") (pinfunction "P2.2/COM2/CSX_B3") (pintype "passive"))
    )
    (net (code "147") (name "unconnected-(IC1B-P2.3{slash}COM3{slash}DCX-PadA3)") (class "Default")
      (node (ref "IC1") (pin "A3") (pinfunction "P2.3/COM3/DCX_A3") (pintype "passive"))
    )
    (net (code "148") (name "unconnected-(IC1B-P2.4{slash}S1{slash}RWX-RDX-PadB4)") (class "Default")
      (node (ref "IC1") (pin "B4") (pinfunction "P2.4/S1/RWX-RDX_B4") (pintype "passive"))
    )
    (net (code "149") (name "unconnected-(IC1B-P2.5{slash}S2{slash}ECLOCK-WRX-PadA4)") (class "Default")
      (node (ref "IC1") (pin "A4") (pinfunction "P2.5/S2/ECLOCK-WRX_A4") (pintype "passive"))
    )
    (net (code "150") (name "unconnected-(IC1B-P2.6{slash}S19{slash}TE-PadD15)") (class "Default")
      (node (ref "IC1") (pin "D15") (pinfunction "P2.6/S19/TE_D15") (pintype "passive"))
    )
    (net (code "151") (name "unconnected-(IC1B-P2.7{slash}S20{slash}TOUTA-PadC15)") (class "Default")
      (node (ref "IC1") (pin "C15") (pinfunction "P2.7/S20/TOUTA_C15") (pintype "passive"))
    )
    (net (code "152") (name "unconnected-(IC1B-P2.8{slash}S21-PadB15)") (class "Default")
      (node (ref "IC1") (pin "B15") (pinfunction "P2.8/S21_B15") (pintype "passive"))
    )
    (net (code "153") (name "unconnected-(IC1B-P2.11{slash}S24-PadB13)") (class "Default")
      (node (ref "IC1") (pin "B13") (pinfunction "P2.11/S24_B13") (pintype "passive"))
    )
    (net (code "154") (name "unconnected-(IC1B-P2.12{slash}S25-PadB14)") (class "Default")
      (node (ref "IC1") (pin "B14") (pinfunction "P2.12/S25_B14") (pintype "passive"))
    )
    (net (code "155") (name "unconnected-(IC1B-P2.13{slash}S26-PadD14)") (class "Default")
      (node (ref "IC1") (pin "D14") (pinfunction "P2.13/S26_D14") (pintype "passive"))
    )
    (net (code "156") (name "unconnected-(IC1B-P2.14{slash}S27-PadE15)") (class "Default")
      (node (ref "IC1") (pin "E15") (pinfunction "P2.14/S27_E15") (pintype "passive"))
    )
    (net (code "157") (name "unconnected-(IC1B-P3.1{slash}SPI0_MISO-PadG14)") (class "Default")
      (node (ref "IC1") (pin "G14") (pinfunction "P3.1/SPI0_MISO_G14") (pintype "passive"))
    )
    (net (code "158") (name "unconnected-(IC1B-P3.8{slash}S29-PadF8)") (class "Default")
      (node (ref "IC1") (pin "F8") (pinfunction "P3.8/S29_F8") (pintype "passive"))
    )
    (net (code "159") (name "unconnected-(IC1B-P3.10{slash}S31-PadC14)") (class "Default")
      (node (ref "IC1") (pin "C14") (pinfunction "P3.10/S31_C14") (pintype "passive"))
    )
    (net (code "160") (name "unconnected-(IC1B-P3.11{slash}S32-PadE14)") (class "Default")
      (node (ref "IC1") (pin "E14") (pinfunction "P3.11/S32_E14") (pintype "passive"))
    )
    (net (code "161") (name "unconnected-(IC1B-P3.12{slash}BEEP{slash}BMCLK-PadK6)") (class "Default")
      (node (ref "IC1") (pin "K6") (pinfunction "P3.12/BEEP/BMCLK_K6") (pintype "passive"))
    )
    (net (code "162") (name "unconnected-(IC1B-P3.13{slash}BEEPX{slash}SDATA-PadK7)") (class "Default")
      (node (ref "IC1") (pin "K7") (pinfunction "P3.13/BEEPX/SDATA_K7") (pintype "passive"))
    )
    (net (code "163") (name "unconnected-(IC1B-P3.14{slash}LRCLK-PadJ6)") (class "Default")
      (node (ref "IC1") (pin "J6") (pinfunction "P3.14/LRCLK_J6") (pintype "passive"))
    )
    (net (code "164") (name "unconnected-(IC1B-P4.0{slash}I2CSCL-PadL1)") (class "Default")
      (node (ref "IC1") (pin "L1") (pinfunction "P4.0/I2CSCL_L1") (pintype "passive"))
    )
    (net (code "165") (name "unconnected-(IC1B-P4.1{slash}I2CSD-PadL2)") (class "Default")
      (node (ref "IC1") (pin "L2") (pinfunction "P4.1/I2CSD_L2") (pintype "passive"))
    )
    (net (code "166") (name "unconnected-(IC1B-P4.2{slash}TOUTB-PadR1)") (class "Default")
      (node (ref "IC1") (pin "R1") (pinfunction "P4.2/TOUTB_R1") (pintype "passive"))
    )
    (net (code "167") (name "unconnected-(IC6-B-Pad5)") (class "Default")
      (node (ref "IC6") (pin "5") (pinfunction "B_5") (pintype "passive"))
    )
    (net (code "168") (name "unconnected-(IC6-RDY-Pad14)") (class "Default")
      (node (ref "IC6") (pin "14") (pinfunction "RDY_14") (pintype "output"))
    )
    (net (code "169") (name "unconnected-(IC6-SDO-Pad13)") (class "Default")
      (node (ref "IC6") (pin "13") (pinfunction "SDO_13") (pintype "output"))
    )
    (net (code "170") (name "unconnected-(JP4-Pad4)") (class "Default")
      (node (ref "JP4") (pin "4") (pinfunction "4_4") (pintype "passive"))
    )
    (net (code "171") (name "unconnected-(JP4-Pad5)") (class "Default")
      (node (ref "JP4") (pin "5") (pinfunction "5_5") (pintype "passive"))
    )
    (net (code "172") (name "unconnected-(JP5-Pad4)") (class "Default")
      (node (ref "JP5") (pin "4") (pinfunction "4_4") (pintype "passive"))
    )
    (net (code "173") (name "unconnected-(JP5-Pad5)") (class "Default")
      (node (ref "JP5") (pin "5") (pinfunction "5_5") (pintype "passive"))
    )
    (net (code "174") (name "unconnected-(PCB1-GEN4{slash}GPIO23-Pad16)") (class "Default")
      (node (ref "PCB1") (pin "16") (pinfunction "GEN4/GPIO23_16") (pintype "bidirectional"))
    )
    (net (code "175") (name "unconnected-(PCB1-GEN5{slash}GPIO24-Pad18)") (class "Default")
      (node (ref "PCB1") (pin "18") (pinfunction "GEN5/GPIO24_18") (pintype "bidirectional"))
    )
    (net (code "176") (name "unconnected-(PCB1-GEN6{slash}GPIO25-Pad22)") (class "Default")
      (node (ref "PCB1") (pin "22") (pinfunction "GEN6/GPIO25_22") (pintype "bidirectional"))
    )
    (net (code "177") (name "unconnected-(PCB1-GPIO04{slash}GCKL-Pad7)") (class "Default")
      (node (ref "PCB1") (pin "7") (pinfunction "GPIO04/GCKL_7") (pintype "bidirectional"))
    )
    (net (code "178") (name "unconnected-(PCB1-GPIO05-Pad29)") (class "Default")
      (node (ref "PCB1") (pin "29") (pinfunction "GPIO05_29") (pintype "bidirectional"))
    )
    (net (code "179") (name "unconnected-(PCB1-GPIO06-Pad31)") (class "Default")
      (node (ref "PCB1") (pin "31") (pinfunction "GPIO06_31") (pintype "bidirectional"))
    )
    (net (code "180") (name "unconnected-(PCB1-GPIO09{slash}MISO-Pad21)") (class "Default")
      (node (ref "PCB1") (pin "21") (pinfunction "GPIO09/MISO_21") (pintype "bidirectional"))
    )
    (net (code "181") (name "unconnected-(PCB1-GPIO10{slash}MOSI-Pad19)") (class "Default")
      (node (ref "PCB1") (pin "19") (pinfunction "GPIO10/MOSI_19") (pintype "bidirectional"))
    )
    (net (code "182") (name "unconnected-(PCB1-GPIO11{slash}SCLK-Pad23)") (class "Default")
      (node (ref "PCB1") (pin "23") (pinfunction "GPIO11/SCLK_23") (pintype "bidirectional"))
    )
    (net (code "183") (name "unconnected-(PCB1-GPIO12-Pad32)") (class "Default")
      (node (ref "PCB1") (pin "32") (pinfunction "GPIO12_32") (pintype "bidirectional"))
    )
    (net (code "184") (name "unconnected-(PCB1-GPIO13-Pad33)") (class "Default")
      (node (ref "PCB1") (pin "33") (pinfunction "GPIO13_33") (pintype "bidirectional"))
    )
    (net (code "185") (name "unconnected-(PCB1-GPIO16-Pad36)") (class "Default")
      (node (ref "PCB1") (pin "36") (pinfunction "GPIO16_36") (pintype "bidirectional"))
    )
    (net (code "186") (name "unconnected-(PCB1-GPIO17{slash}GEN0-Pad11)") (class "Default")
      (node (ref "PCB1") (pin "11") (pinfunction "GPIO17/GEN0_11") (pintype "bidirectional"))
    )
    (net (code "187") (name "unconnected-(PCB1-GPIO18-Pad12)") (class "Default")
      (node (ref "PCB1") (pin "12") (pinfunction "GPIO18_12") (pintype "bidirectional"))
    )
    (net (code "188") (name "unconnected-(PCB1-GPIO19-Pad35)") (class "Default")
      (node (ref "PCB1") (pin "35") (pinfunction "GPIO19_35") (pintype "bidirectional"))
    )
    (net (code "189") (name "unconnected-(PCB1-GPIO22{slash}GEN3-Pad15)") (class "Default")
      (node (ref "PCB1") (pin "15") (pinfunction "GPIO22/GEN3_15") (pintype "bidirectional"))
    )
    (net (code "190") (name "unconnected-(PCB1-GPIO26-Pad37)") (class "Default")
      (node (ref "PCB1") (pin "37") (pinfunction "GPIO26_37") (pintype "bidirectional"))
    )
    (net (code "191") (name "unconnected-(PCB1-GPIO27{slash}GEN2-Pad13)") (class "Default")
      (node (ref "PCB1") (pin "13") (pinfunction "GPIO27/GEN2_13") (pintype "bidirectional"))
    )
    (net (code "192") (name "unconnected-(PCB1-~{CE0}{slash}GPIO08-Pad24)") (class "Default")
      (node (ref "PCB1") (pin "24") (pinfunction "~{CE0}/GPIO08_24") (pintype "bidirectional"))
    )
    (net (code "193") (name "unconnected-(PCB1-~{CE}{slash}GPIO07-Pad26)") (class "Default")
      (node (ref "PCB1") (pin "26") (pinfunction "~{CE}/GPIO07_26") (pintype "bidirectional"))
    )
    (net (code "194") (name "unconnected-(X1-PadA6)") (class "Default")
      (node (ref "X1") (pin "A6") (pinfunction "A6_A6") (pintype "passive"))
    )
    (net (code "195") (name "unconnected-(X1-PadA7)") (class "Default")
      (node (ref "X1") (pin "A7") (pinfunction "A7_A7") (pintype "passive"))
    )
    (net (code "196") (name "unconnected-(X1-PadB18)") (class "Default")
      (node (ref "X1") (pin "B18") (pinfunction "B18_B18") (pintype "passive"))
    )
    (net (code "197") (name "unconnected-(X2-PadA1)") (class "Default")
      (node (ref "X2") (pin "A1") (pinfunction "A1_A1") (pintype "passive"))
    )
    (net (code "198") (name "unconnected-(X2-PadA2)") (class "Default")
      (node (ref "X2") (pin "A2") (pinfunction "A2_A2") (pintype "passive"))
    )
    (net (code "199") (name "unconnected-(X2-PadA3)") (class "Default")
      (node (ref "X2") (pin "A3") (pinfunction "A3_A3") (pintype "passive"))
    )
    (net (code "200") (name "unconnected-(X2-PadA4)") (class "Default")
      (node (ref "X2") (pin "A4") (pinfunction "A4_A4") (pintype "passive"))
    )
    (net (code "201") (name "unconnected-(X2-PadA5)") (class "Default")
      (node (ref "X2") (pin "A5") (pinfunction "A5_A5") (pintype "passive"))
    )
    (net (code "202") (name "unconnected-(X2-PadA6)") (class "Default")
      (node (ref "X2") (pin "A6") (pinfunction "A6_A6") (pintype "passive"))
    )
    (net (code "203") (name "unconnected-(X2-PadA7)") (class "Default")
      (node (ref "X2") (pin "A7") (pinfunction "A7_A7") (pintype "passive"))
    )
    (net (code "204") (name "unconnected-(X2-PadA8)") (class "Default")
      (node (ref "X2") (pin "A8") (pinfunction "A8_A8") (pintype "passive"))
    )
    (net (code "205") (name "unconnected-(X2-PadA9)") (class "Default")
      (node (ref "X2") (pin "A9") (pinfunction "A9_A9") (pintype "passive"))
    )
    (net (code "206") (name "unconnected-(X2-PadA11)") (class "Default")
      (node (ref "X2") (pin "A11") (pinfunction "A11_A11") (pintype "passive"))
    )
    (net (code "207") (name "unconnected-(X2-PadA12)") (class "Default")
      (node (ref "X2") (pin "A12") (pinfunction "A12_A12") (pintype "passive"))
    )
    (net (code "208") (name "unconnected-(X2-PadA13)") (class "Default")
      (node (ref "X2") (pin "A13") (pinfunction "A13_A13") (pintype "passive"))
    )
    (net (code "209") (name "unconnected-(X2-PadA15)") (class "Default")
      (node (ref "X2") (pin "A15") (pinfunction "A15_A15") (pintype "passive"))
    )
    (net (code "210") (name "unconnected-(X2-PadA17)") (class "Default")
      (node (ref "X2") (pin "A17") (pinfunction "A17_A17") (pintype "passive"))
    )
    (net (code "211") (name "unconnected-(X2-PadA18)") (class "Default")
      (node (ref "X2") (pin "A18") (pinfunction "A18_A18") (pintype "passive"))
    )
    (net (code "212") (name "unconnected-(X2-PadB5)") (class "Default")
      (node (ref "X2") (pin "B5") (pinfunction "B5_B5") (pintype "passive"))
    )
    (net (code "213") (name "unconnected-(X2-PadB13)") (class "Default")
      (node (ref "X2") (pin "B13") (pinfunction "B13_B13") (pintype "passive"))
    )
    (net (code "214") (name "unconnected-(X2-PadB18)") (class "Default")
      (node (ref "X2") (pin "B18") (pinfunction "B18_B18") (pintype "passive"))
    )
  )
)
